# iso_lvds_tx.net
KiCad netlist of a schematic drawn in Altium Designer
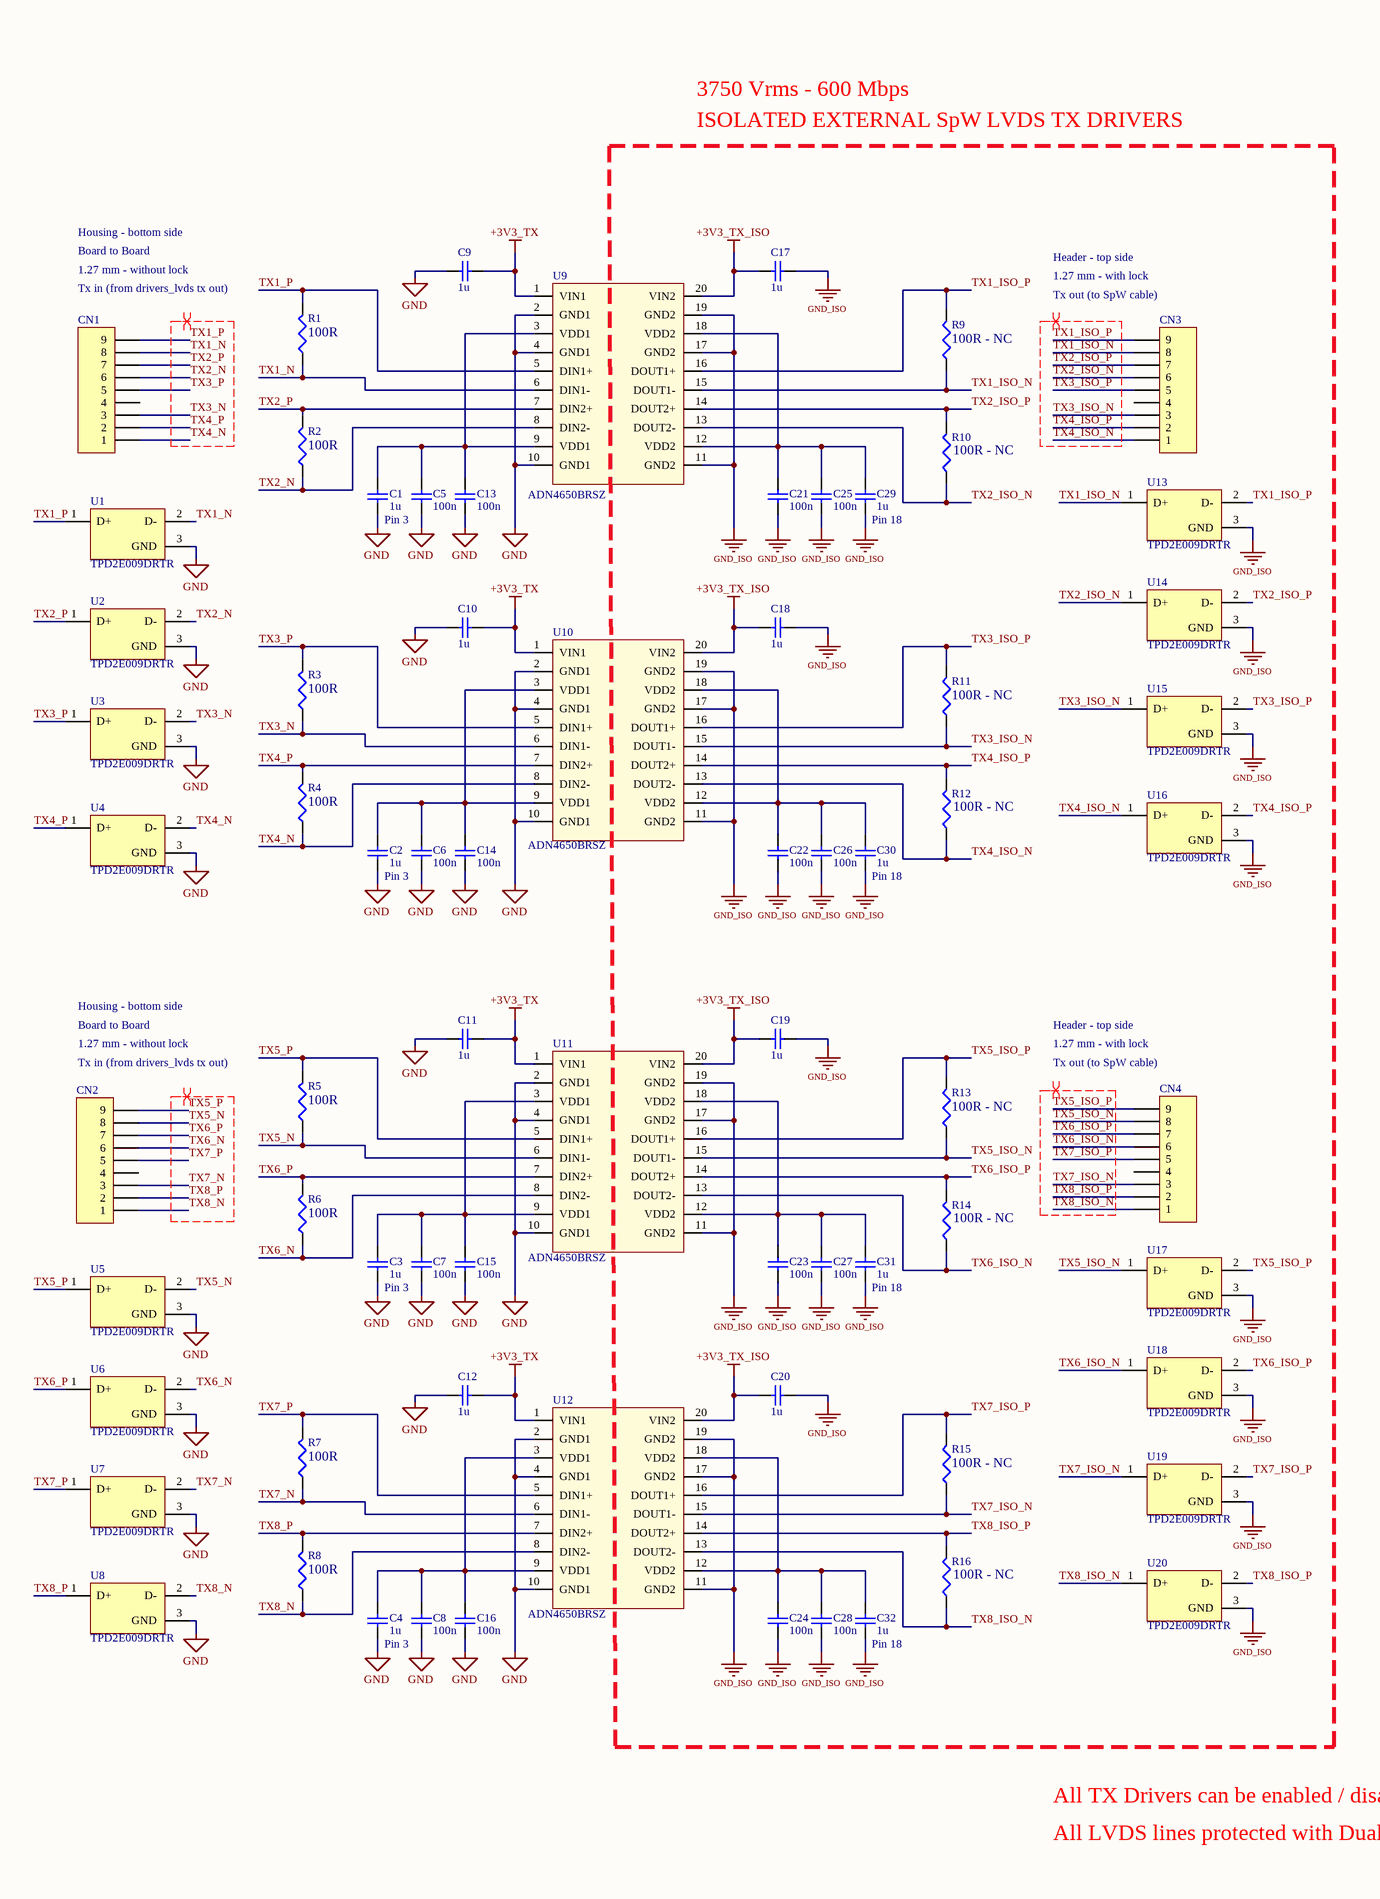
[diagram p0: iso_lvds_tx.SchDoc, left]
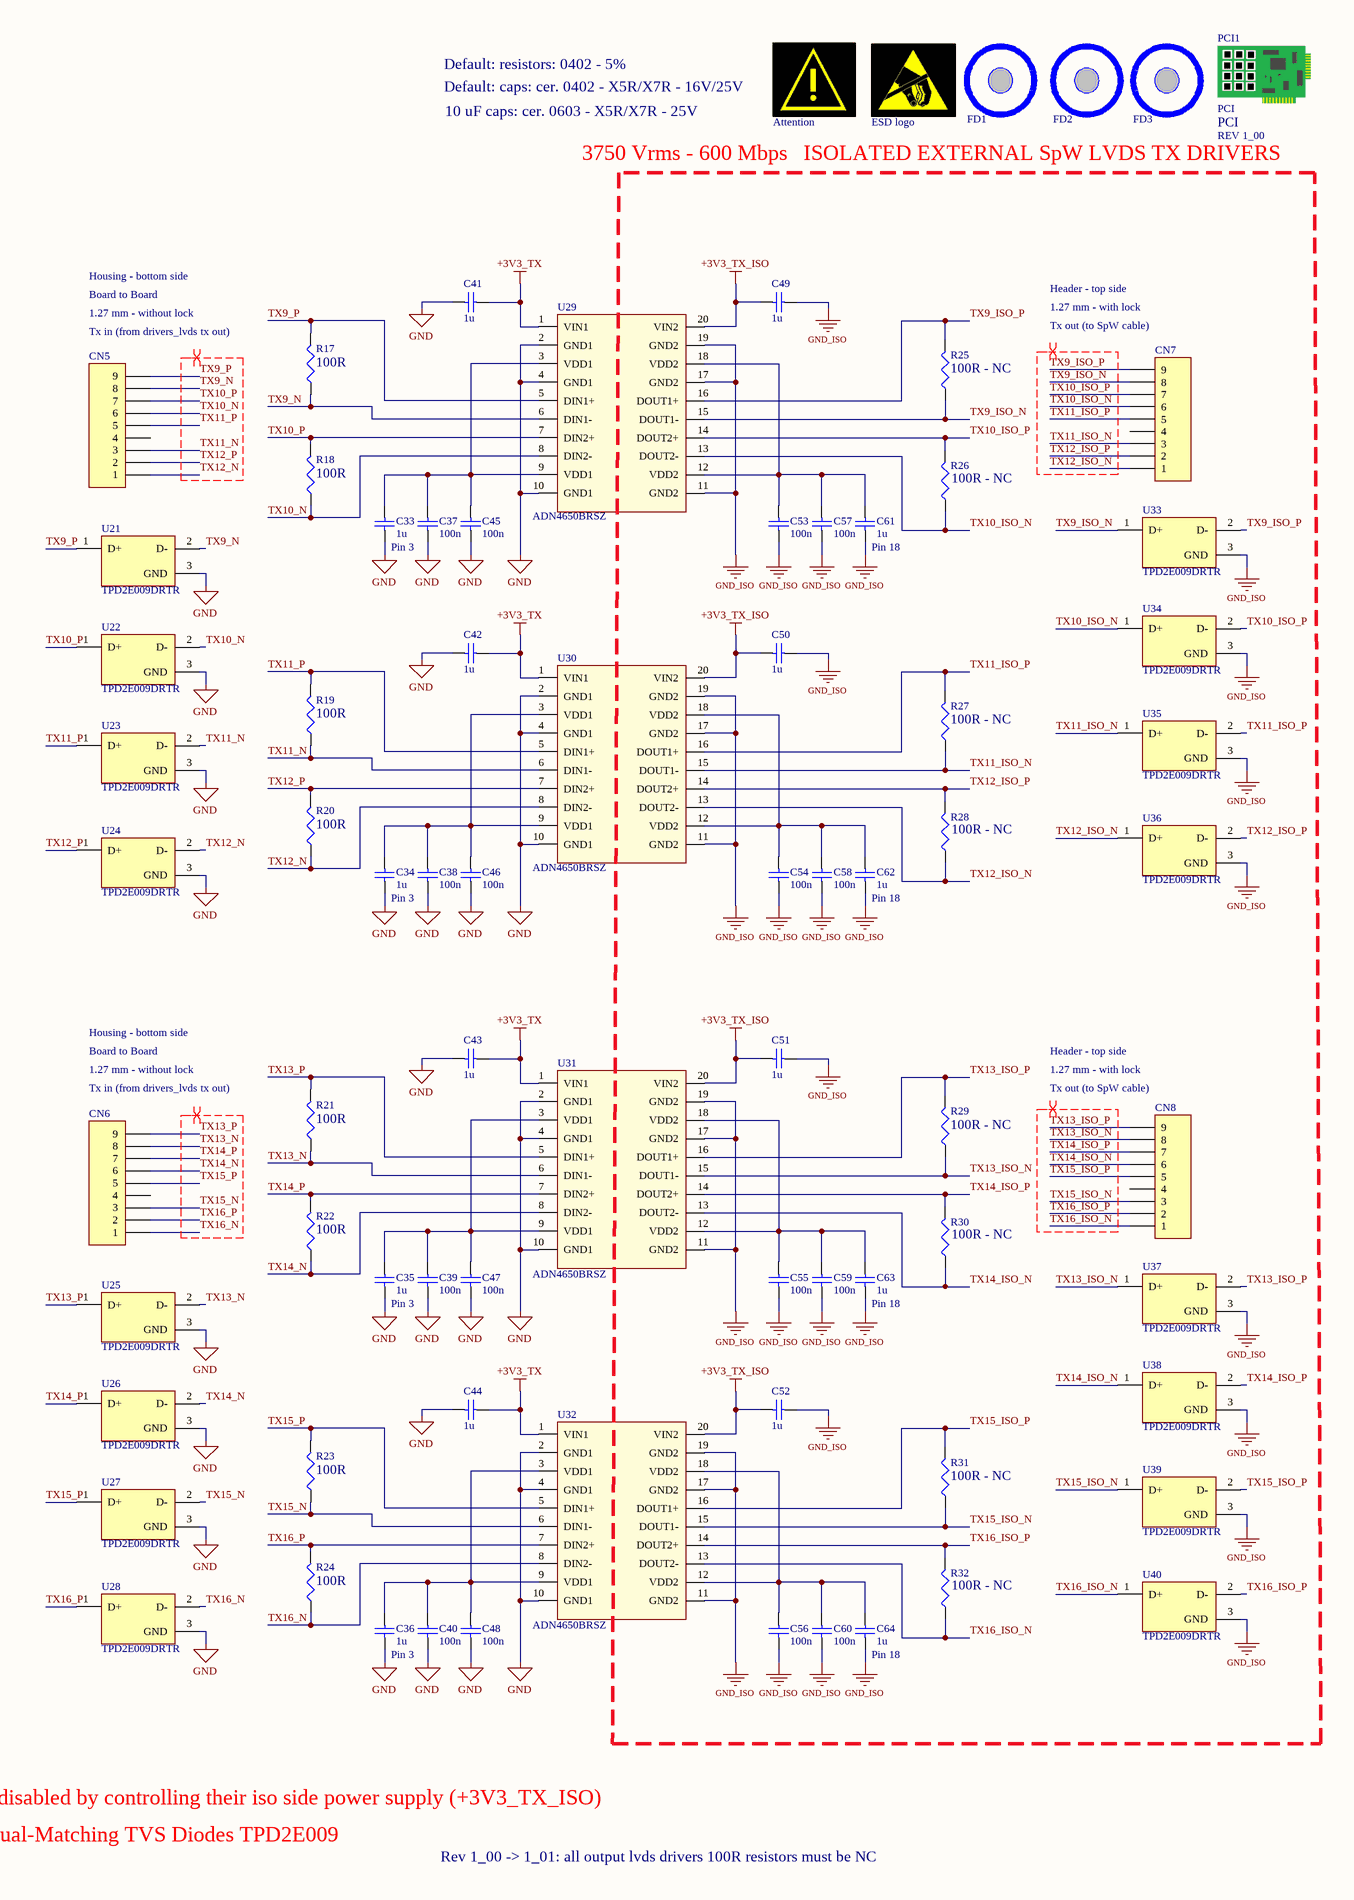
[diagram p1: iso_lvds_tx.SchDoc, right]

(export (version "E")
  (design (tool "Eeschema 10.0.6"))
  (components
    (comp (ref "AT1")
      (value "##nl")
      (footprint "LEIA_DOCUMENTACAO")
      (description "ATENCAO")
      (fields (field (name "VALOR") "Attention"))
      (libsource (lib "SIMBOLOS") (part "ATENCAO"))
    )
    (comp (ref "C1")
      (value "Capacitor Cerâmico SMD")
      (footprint "0402-cap")
      (fields (field (name "VALOR") "1u"))
      (libsource (lib "Miscellaneous Devices") (part "Capacitor Cerâmico SMD"))
    )
    (comp (ref "C2")
      (value "Capacitor Cerâmico SMD")
      (footprint "0402-cap")
      (fields (field (name "VALOR") "1u"))
      (libsource (lib "Miscellaneous Devices") (part "Capacitor Cerâmico SMD"))
    )
    (comp (ref "C3")
      (value "Capacitor Cerâmico SMD")
      (footprint "0402-cap")
      (fields (field (name "VALOR") "1u"))
      (libsource (lib "Miscellaneous Devices") (part "Capacitor Cerâmico SMD"))
    )
    (comp (ref "C4")
      (value "Capacitor Cerâmico SMD")
      (footprint "0402-cap")
      (fields (field (name "VALOR") "1u"))
      (libsource (lib "Miscellaneous Devices") (part "Capacitor Cerâmico SMD"))
    )
    (comp (ref "C5")
      (value "Capacitor Cerâmico SMD")
      (footprint "0402-cap")
      (fields (field (name "VALOR") "100n"))
      (libsource (lib "Miscellaneous Devices") (part "Capacitor Cerâmico SMD"))
    )
    (comp (ref "C6")
      (value "Capacitor Cerâmico SMD")
      (footprint "0402-cap")
      (fields (field (name "VALOR") "100n"))
      (libsource (lib "Miscellaneous Devices") (part "Capacitor Cerâmico SMD"))
    )
    (comp (ref "C7")
      (value "Capacitor Cerâmico SMD")
      (footprint "0402-cap")
      (fields (field (name "VALOR") "100n"))
      (libsource (lib "Miscellaneous Devices") (part "Capacitor Cerâmico SMD"))
    )
    (comp (ref "C8")
      (value "Capacitor Cerâmico SMD")
      (footprint "0402-cap")
      (fields (field (name "VALOR") "100n"))
      (libsource (lib "Miscellaneous Devices") (part "Capacitor Cerâmico SMD"))
    )
    (comp (ref "C9")
      (value "Capacitor Cerâmico SMD")
      (footprint "0402-cap")
      (fields (field (name "VALOR") "1u"))
      (libsource (lib "Miscellaneous Devices") (part "Capacitor Cerâmico SMD"))
    )
    (comp (ref "C10")
      (value "Capacitor Cerâmico SMD")
      (footprint "0402-cap")
      (fields (field (name "VALOR") "1u"))
      (libsource (lib "Miscellaneous Devices") (part "Capacitor Cerâmico SMD"))
    )
    (comp (ref "C11")
      (value "Capacitor Cerâmico SMD")
      (footprint "0402-cap")
      (fields (field (name "VALOR") "1u"))
      (libsource (lib "Miscellaneous Devices") (part "Capacitor Cerâmico SMD"))
    )
    (comp (ref "C12")
      (value "Capacitor Cerâmico SMD")
      (footprint "0402-cap")
      (fields (field (name "VALOR") "1u"))
      (libsource (lib "Miscellaneous Devices") (part "Capacitor Cerâmico SMD"))
    )
    (comp (ref "C13")
      (value "Capacitor Cerâmico SMD")
      (footprint "0402-cap")
      (fields (field (name "VALOR") "100n"))
      (libsource (lib "Miscellaneous Devices") (part "Capacitor Cerâmico SMD"))
    )
    (comp (ref "C14")
      (value "Capacitor Cerâmico SMD")
      (footprint "0402-cap")
      (fields (field (name "VALOR") "100n"))
      (libsource (lib "Miscellaneous Devices") (part "Capacitor Cerâmico SMD"))
    )
    (comp (ref "C15")
      (value "Capacitor Cerâmico SMD")
      (footprint "0402-cap")
      (fields (field (name "VALOR") "100n"))
      (libsource (lib "Miscellaneous Devices") (part "Capacitor Cerâmico SMD"))
    )
    (comp (ref "C16")
      (value "Capacitor Cerâmico SMD")
      (footprint "0402-cap")
      (fields (field (name "VALOR") "100n"))
      (libsource (lib "Miscellaneous Devices") (part "Capacitor Cerâmico SMD"))
    )
    (comp (ref "C17")
      (value "Capacitor Cerâmico SMD")
      (footprint "0402-cap")
      (fields (field (name "VALOR") "1u"))
      (libsource (lib "Miscellaneous Devices") (part "Capacitor Cerâmico SMD"))
    )
    (comp (ref "C18")
      (value "Capacitor Cerâmico SMD")
      (footprint "0402-cap")
      (fields (field (name "VALOR") "1u"))
      (libsource (lib "Miscellaneous Devices") (part "Capacitor Cerâmico SMD"))
    )
    (comp (ref "C19")
      (value "Capacitor Cerâmico SMD")
      (footprint "0402-cap")
      (fields (field (name "VALOR") "1u"))
      (libsource (lib "Miscellaneous Devices") (part "Capacitor Cerâmico SMD"))
    )
    (comp (ref "C20")
      (value "Capacitor Cerâmico SMD")
      (footprint "0402-cap")
      (fields (field (name "VALOR") "1u"))
      (libsource (lib "Miscellaneous Devices") (part "Capacitor Cerâmico SMD"))
    )
    (comp (ref "C21")
      (value "Capacitor Cerâmico SMD")
      (footprint "0402-cap")
      (fields (field (name "VALOR") "100n"))
      (libsource (lib "Miscellaneous Devices") (part "Capacitor Cerâmico SMD"))
    )
    (comp (ref "C22")
      (value "Capacitor Cerâmico SMD")
      (footprint "0402-cap")
      (fields (field (name "VALOR") "100n"))
      (libsource (lib "Miscellaneous Devices") (part "Capacitor Cerâmico SMD"))
    )
    (comp (ref "C23")
      (value "Capacitor Cerâmico SMD")
      (footprint "0402-cap")
      (fields (field (name "VALOR") "100n"))
      (libsource (lib "Miscellaneous Devices") (part "Capacitor Cerâmico SMD"))
    )
    (comp (ref "C24")
      (value "Capacitor Cerâmico SMD")
      (footprint "0402-cap")
      (fields (field (name "VALOR") "100n"))
      (libsource (lib "Miscellaneous Devices") (part "Capacitor Cerâmico SMD"))
    )
    (comp (ref "C25")
      (value "Capacitor Cerâmico SMD")
      (footprint "0402-cap")
      (fields (field (name "VALOR") "100n"))
      (libsource (lib "Miscellaneous Devices") (part "Capacitor Cerâmico SMD"))
    )
    (comp (ref "C26")
      (value "Capacitor Cerâmico SMD")
      (footprint "0402-cap")
      (fields (field (name "VALOR") "100n"))
      (libsource (lib "Miscellaneous Devices") (part "Capacitor Cerâmico SMD"))
    )
    (comp (ref "C27")
      (value "Capacitor Cerâmico SMD")
      (footprint "0402-cap")
      (fields (field (name "VALOR") "100n"))
      (libsource (lib "Miscellaneous Devices") (part "Capacitor Cerâmico SMD"))
    )
    (comp (ref "C28")
      (value "Capacitor Cerâmico SMD")
      (footprint "0402-cap")
      (fields (field (name "VALOR") "100n"))
      (libsource (lib "Miscellaneous Devices") (part "Capacitor Cerâmico SMD"))
    )
    (comp (ref "C29")
      (value "Capacitor Cerâmico SMD")
      (footprint "0402-cap")
      (fields (field (name "VALOR") "1u"))
      (libsource (lib "Miscellaneous Devices") (part "Capacitor Cerâmico SMD"))
    )
    (comp (ref "C30")
      (value "Capacitor Cerâmico SMD")
      (footprint "0402-cap")
      (fields (field (name "VALOR") "1u"))
      (libsource (lib "Miscellaneous Devices") (part "Capacitor Cerâmico SMD"))
    )
    (comp (ref "C31")
      (value "Capacitor Cerâmico SMD")
      (footprint "0402-cap")
      (fields (field (name "VALOR") "1u"))
      (libsource (lib "Miscellaneous Devices") (part "Capacitor Cerâmico SMD"))
    )
    (comp (ref "C32")
      (value "Capacitor Cerâmico SMD")
      (footprint "0402-cap")
      (fields (field (name "VALOR") "1u"))
      (libsource (lib "Miscellaneous Devices") (part "Capacitor Cerâmico SMD"))
    )
    (comp (ref "C33")
      (value "Capacitor Cerâmico SMD")
      (footprint "0402-cap")
      (fields (field (name "VALOR") "1u"))
      (libsource (lib "Miscellaneous Devices") (part "Capacitor Cerâmico SMD"))
    )
    (comp (ref "C34")
      (value "Capacitor Cerâmico SMD")
      (footprint "0402-cap")
      (fields (field (name "VALOR") "1u"))
      (libsource (lib "Miscellaneous Devices") (part "Capacitor Cerâmico SMD"))
    )
    (comp (ref "C35")
      (value "Capacitor Cerâmico SMD")
      (footprint "0402-cap")
      (fields (field (name "VALOR") "1u"))
      (libsource (lib "Miscellaneous Devices") (part "Capacitor Cerâmico SMD"))
    )
    (comp (ref "C36")
      (value "Capacitor Cerâmico SMD")
      (footprint "0402-cap")
      (fields (field (name "VALOR") "1u"))
      (libsource (lib "Miscellaneous Devices") (part "Capacitor Cerâmico SMD"))
    )
    (comp (ref "C37")
      (value "Capacitor Cerâmico SMD")
      (footprint "0402-cap")
      (fields (field (name "VALOR") "100n"))
      (libsource (lib "Miscellaneous Devices") (part "Capacitor Cerâmico SMD"))
    )
    (comp (ref "C38")
      (value "Capacitor Cerâmico SMD")
      (footprint "0402-cap")
      (fields (field (name "VALOR") "100n"))
      (libsource (lib "Miscellaneous Devices") (part "Capacitor Cerâmico SMD"))
    )
    (comp (ref "C39")
      (value "Capacitor Cerâmico SMD")
      (footprint "0402-cap")
      (fields (field (name "VALOR") "100n"))
      (libsource (lib "Miscellaneous Devices") (part "Capacitor Cerâmico SMD"))
    )
    (comp (ref "C40")
      (value "Capacitor Cerâmico SMD")
      (footprint "0402-cap")
      (fields (field (name "VALOR") "100n"))
      (libsource (lib "Miscellaneous Devices") (part "Capacitor Cerâmico SMD"))
    )
    (comp (ref "C41")
      (value "Capacitor Cerâmico SMD")
      (footprint "0402-cap")
      (fields (field (name "VALOR") "1u"))
      (libsource (lib "Miscellaneous Devices") (part "Capacitor Cerâmico SMD"))
    )
    (comp (ref "C42")
      (value "Capacitor Cerâmico SMD")
      (footprint "0402-cap")
      (fields (field (name "VALOR") "1u"))
      (libsource (lib "Miscellaneous Devices") (part "Capacitor Cerâmico SMD"))
    )
    (comp (ref "C43")
      (value "Capacitor Cerâmico SMD")
      (footprint "0402-cap")
      (fields (field (name "VALOR") "1u"))
      (libsource (lib "Miscellaneous Devices") (part "Capacitor Cerâmico SMD"))
    )
    (comp (ref "C44")
      (value "Capacitor Cerâmico SMD")
      (footprint "0402-cap")
      (fields (field (name "VALOR") "1u"))
      (libsource (lib "Miscellaneous Devices") (part "Capacitor Cerâmico SMD"))
    )
    (comp (ref "C45")
      (value "Capacitor Cerâmico SMD")
      (footprint "0402-cap")
      (fields (field (name "VALOR") "100n"))
      (libsource (lib "Miscellaneous Devices") (part "Capacitor Cerâmico SMD"))
    )
    (comp (ref "C46")
      (value "Capacitor Cerâmico SMD")
      (footprint "0402-cap")
      (fields (field (name "VALOR") "100n"))
      (libsource (lib "Miscellaneous Devices") (part "Capacitor Cerâmico SMD"))
    )
    (comp (ref "C47")
      (value "Capacitor Cerâmico SMD")
      (footprint "0402-cap")
      (fields (field (name "VALOR") "100n"))
      (libsource (lib "Miscellaneous Devices") (part "Capacitor Cerâmico SMD"))
    )
    (comp (ref "C48")
      (value "Capacitor Cerâmico SMD")
      (footprint "0402-cap")
      (fields (field (name "VALOR") "100n"))
      (libsource (lib "Miscellaneous Devices") (part "Capacitor Cerâmico SMD"))
    )
    (comp (ref "C49")
      (value "Capacitor Cerâmico SMD")
      (footprint "0402-cap")
      (fields (field (name "VALOR") "1u"))
      (libsource (lib "Miscellaneous Devices") (part "Capacitor Cerâmico SMD"))
    )
    (comp (ref "C50")
      (value "Capacitor Cerâmico SMD")
      (footprint "0402-cap")
      (fields (field (name "VALOR") "1u"))
      (libsource (lib "Miscellaneous Devices") (part "Capacitor Cerâmico SMD"))
    )
    (comp (ref "C51")
      (value "Capacitor Cerâmico SMD")
      (footprint "0402-cap")
      (fields (field (name "VALOR") "1u"))
      (libsource (lib "Miscellaneous Devices") (part "Capacitor Cerâmico SMD"))
    )
    (comp (ref "C52")
      (value "Capacitor Cerâmico SMD")
      (footprint "0402-cap")
      (fields (field (name "VALOR") "1u"))
      (libsource (lib "Miscellaneous Devices") (part "Capacitor Cerâmico SMD"))
    )
    (comp (ref "C53")
      (value "Capacitor Cerâmico SMD")
      (footprint "0402-cap")
      (fields (field (name "VALOR") "100n"))
      (libsource (lib "Miscellaneous Devices") (part "Capacitor Cerâmico SMD"))
    )
    (comp (ref "C54")
      (value "Capacitor Cerâmico SMD")
      (footprint "0402-cap")
      (fields (field (name "VALOR") "100n"))
      (libsource (lib "Miscellaneous Devices") (part "Capacitor Cerâmico SMD"))
    )
    (comp (ref "C55")
      (value "Capacitor Cerâmico SMD")
      (footprint "0402-cap")
      (fields (field (name "VALOR") "100n"))
      (libsource (lib "Miscellaneous Devices") (part "Capacitor Cerâmico SMD"))
    )
    (comp (ref "C56")
      (value "Capacitor Cerâmico SMD")
      (footprint "0402-cap")
      (fields (field (name "VALOR") "100n"))
      (libsource (lib "Miscellaneous Devices") (part "Capacitor Cerâmico SMD"))
    )
    (comp (ref "C57")
      (value "Capacitor Cerâmico SMD")
      (footprint "0402-cap")
      (fields (field (name "VALOR") "100n"))
      (libsource (lib "Miscellaneous Devices") (part "Capacitor Cerâmico SMD"))
    )
    (comp (ref "C58")
      (value "Capacitor Cerâmico SMD")
      (footprint "0402-cap")
      (fields (field (name "VALOR") "100n"))
      (libsource (lib "Miscellaneous Devices") (part "Capacitor Cerâmico SMD"))
    )
    (comp (ref "C59")
      (value "Capacitor Cerâmico SMD")
      (footprint "0402-cap")
      (fields (field (name "VALOR") "100n"))
      (libsource (lib "Miscellaneous Devices") (part "Capacitor Cerâmico SMD"))
    )
    (comp (ref "C60")
      (value "Capacitor Cerâmico SMD")
      (footprint "0402-cap")
      (fields (field (name "VALOR") "100n"))
      (libsource (lib "Miscellaneous Devices") (part "Capacitor Cerâmico SMD"))
    )
    (comp (ref "C61")
      (value "Capacitor Cerâmico SMD")
      (footprint "0402-cap")
      (fields (field (name "VALOR") "1u"))
      (libsource (lib "Miscellaneous Devices") (part "Capacitor Cerâmico SMD"))
    )
    (comp (ref "C62")
      (value "Capacitor Cerâmico SMD")
      (footprint "0402-cap")
      (fields (field (name "VALOR") "1u"))
      (libsource (lib "Miscellaneous Devices") (part "Capacitor Cerâmico SMD"))
    )
    (comp (ref "C63")
      (value "Capacitor Cerâmico SMD")
      (footprint "0402-cap")
      (fields (field (name "VALOR") "1u"))
      (libsource (lib "Miscellaneous Devices") (part "Capacitor Cerâmico SMD"))
    )
    (comp (ref "C64")
      (value "Capacitor Cerâmico SMD")
      (footprint "0402-cap")
      (fields (field (name "VALOR") "1u"))
      (libsource (lib "Miscellaneous Devices") (part "Capacitor Cerâmico SMD"))
    )
    (comp (ref "CN1")
      (value "MHDR1X9")
      (footprint "MHDR1X9_Axonn")
      (description "Header, 9-Pin")
      (fields (field (name "PUBLISHER") "Altium Limited"))
      (libsource (lib "") (part "MHDR1X9_1"))
    )
    (comp (ref "CN2")
      (value "MHDR1X9")
      (footprint "MHDR1X9_Axonn")
      (description "Header, 9-Pin")
      (fields (field (name "PUBLISHER") "Altium Limited"))
      (libsource (lib "") (part "MHDR1X9_1"))
    )
    (comp (ref "CN3")
      (value "MHDR1X9")
      (footprint "MHDR1X9_Axonn")
      (description "Header, 9-Pin")
      (fields (field (name "PUBLISHER") "Altium Limited"))
      (libsource (lib "Miscellaneous Connectors") (part "MHDR1X9"))
    )
    (comp (ref "CN4")
      (value "MHDR1X9")
      (footprint "MHDR1X9_Axonn")
      (description "Header, 9-Pin")
      (fields (field (name "PUBLISHER") "Altium Limited"))
      (libsource (lib "Miscellaneous Connectors") (part "MHDR1X9"))
    )
    (comp (ref "CN5")
      (value "MHDR1X9")
      (footprint "MHDR1X9_Axonn")
      (description "Header, 9-Pin")
      (fields (field (name "PUBLISHER") "Altium Limited"))
      (libsource (lib "") (part "MHDR1X9_1"))
    )
    (comp (ref "CN6")
      (value "MHDR1X9")
      (footprint "MHDR1X9_Axonn")
      (description "Header, 9-Pin")
      (fields (field (name "PUBLISHER") "Altium Limited"))
      (libsource (lib "") (part "MHDR1X9_1"))
    )
    (comp (ref "CN7")
      (value "MHDR1X9")
      (footprint "MHDR1X9_Axonn")
      (description "Header, 9-Pin")
      (fields (field (name "PUBLISHER") "Altium Limited"))
      (libsource (lib "Miscellaneous Connectors") (part "MHDR1X9"))
    )
    (comp (ref "CN8")
      (value "MHDR1X9")
      (footprint "MHDR1X9_Axonn")
      (description "Header, 9-Pin")
      (fields (field (name "PUBLISHER") "Altium Limited"))
      (libsource (lib "Miscellaneous Connectors") (part "MHDR1X9"))
    )
    (comp (ref "ESD1")
      (value "##nl")
      (footprint "ESTATICA")
      (description "ESD")
      (fields (field (name "VALOR") "ESD logo"))
      (libsource (lib "SIMBOLOS") (part "ESD"))
    )
    (comp (ref "FD1")
      (value "##nl")
      (footprint "FIDUCIAL")
      (description "Fiducial")
      (libsource (lib "PERIFERICOS") (part "Fiducial"))
    )
    (comp (ref "FD2")
      (value "##nl")
      (footprint "FIDUCIAL")
      (description "Fiducial")
      (libsource (lib "PERIFERICOS") (part "Fiducial"))
    )
    (comp (ref "FD3")
      (value "##nl")
      (footprint "FIDUCIAL")
      (description "Fiducial")
      (libsource (lib "PERIFERICOS") (part "Fiducial"))
    )
    (comp (ref "PCI1")
      (value "PCI")
      (fields (field (name "VALOR") "PCI") (field (name "REV") "REV 1_00"))
      (libsource (lib "PCI") (part "PCI"))
    )
    (comp (ref "R1")
      (value "Res3")
      (footprint "0402-res")
      (description "Resistor")
      (fields (field (name "VALOR") "100R"))
      (libsource (lib "Miscellaneous Devices") (part "Res3"))
    )
    (comp (ref "R2")
      (value "Res3")
      (footprint "0402-res")
      (description "Resistor")
      (fields (field (name "VALOR") "100R"))
      (libsource (lib "Miscellaneous Devices") (part "Res3"))
    )
    (comp (ref "R3")
      (value "Res3")
      (footprint "0402-res")
      (description "Resistor")
      (fields (field (name "VALOR") "100R"))
      (libsource (lib "Miscellaneous Devices") (part "Res3"))
    )
    (comp (ref "R4")
      (value "Res3")
      (footprint "0402-res")
      (description "Resistor")
      (fields (field (name "VALOR") "100R"))
      (libsource (lib "Miscellaneous Devices") (part "Res3"))
    )
    (comp (ref "R5")
      (value "Res3")
      (footprint "0402-res")
      (description "Resistor")
      (fields (field (name "VALOR") "100R"))
      (libsource (lib "Miscellaneous Devices") (part "Res3"))
    )
    (comp (ref "R6")
      (value "Res3")
      (footprint "0402-res")
      (description "Resistor")
      (fields (field (name "VALOR") "100R"))
      (libsource (lib "Miscellaneous Devices") (part "Res3"))
    )
    (comp (ref "R7")
      (value "Res3")
      (footprint "0402-res")
      (description "Resistor")
      (fields (field (name "VALOR") "100R"))
      (libsource (lib "Miscellaneous Devices") (part "Res3"))
    )
    (comp (ref "R8")
      (value "Res3")
      (footprint "0402-res")
      (description "Resistor")
      (fields (field (name "VALOR") "100R"))
      (libsource (lib "Miscellaneous Devices") (part "Res3"))
    )
    (comp (ref "R9")
      (value "Res3")
      (footprint "0402-res")
      (description "Resistor")
      (fields (field (name "VALOR") "100R - NC"))
      (libsource (lib "Miscellaneous Devices") (part "Res3"))
    )
    (comp (ref "R10")
      (value "Res3")
      (footprint "0402-res")
      (description "Resistor")
      (fields (field (name "VALOR") "100R - NC"))
      (libsource (lib "Miscellaneous Devices") (part "Res3"))
    )
    (comp (ref "R11")
      (value "Res3")
      (footprint "0402-res")
      (description "Resistor")
      (fields (field (name "VALOR") "100R - NC"))
      (libsource (lib "Miscellaneous Devices") (part "Res3"))
    )
    (comp (ref "R12")
      (value "Res3")
      (footprint "0402-res")
      (description "Resistor")
      (fields (field (name "VALOR") "100R - NC"))
      (libsource (lib "Miscellaneous Devices") (part "Res3"))
    )
    (comp (ref "R13")
      (value "Res3")
      (footprint "0402-res")
      (description "Resistor")
      (fields (field (name "VALOR") "100R - NC"))
      (libsource (lib "Miscellaneous Devices") (part "Res3"))
    )
    (comp (ref "R14")
      (value "Res3")
      (footprint "0402-res")
      (description "Resistor")
      (fields (field (name "VALOR") "100R - NC"))
      (libsource (lib "Miscellaneous Devices") (part "Res3"))
    )
    (comp (ref "R15")
      (value "Res3")
      (footprint "0402-res")
      (description "Resistor")
      (fields (field (name "VALOR") "100R - NC"))
      (libsource (lib "Miscellaneous Devices") (part "Res3"))
    )
    (comp (ref "R16")
      (value "Res3")
      (footprint "0402-res")
      (description "Resistor")
      (fields (field (name "VALOR") "100R - NC"))
      (libsource (lib "Miscellaneous Devices") (part "Res3"))
    )
    (comp (ref "R17")
      (value "Res3")
      (footprint "0402-res")
      (description "Resistor")
      (fields (field (name "VALOR") "100R"))
      (libsource (lib "Miscellaneous Devices") (part "Res3"))
    )
    (comp (ref "R18")
      (value "Res3")
      (footprint "0402-res")
      (description "Resistor")
      (fields (field (name "VALOR") "100R"))
      (libsource (lib "Miscellaneous Devices") (part "Res3"))
    )
    (comp (ref "R19")
      (value "Res3")
      (footprint "0402-res")
      (description "Resistor")
      (fields (field (name "VALOR") "100R"))
      (libsource (lib "Miscellaneous Devices") (part "Res3"))
    )
    (comp (ref "R20")
      (value "Res3")
      (footprint "0402-res")
      (description "Resistor")
      (fields (field (name "VALOR") "100R"))
      (libsource (lib "Miscellaneous Devices") (part "Res3"))
    )
    (comp (ref "R21")
      (value "Res3")
      (footprint "0402-res")
      (description "Resistor")
      (fields (field (name "VALOR") "100R"))
      (libsource (lib "Miscellaneous Devices") (part "Res3"))
    )
    (comp (ref "R22")
      (value "Res3")
      (footprint "0402-res")
      (description "Resistor")
      (fields (field (name "VALOR") "100R"))
      (libsource (lib "Miscellaneous Devices") (part "Res3"))
    )
    (comp (ref "R23")
      (value "Res3")
      (footprint "0402-res")
      (description "Resistor")
      (fields (field (name "VALOR") "100R"))
      (libsource (lib "Miscellaneous Devices") (part "Res3"))
    )
    (comp (ref "R24")
      (value "Res3")
      (footprint "0402-res")
      (description "Resistor")
      (fields (field (name "VALOR") "100R"))
      (libsource (lib "Miscellaneous Devices") (part "Res3"))
    )
    (comp (ref "R25")
      (value "Res3")
      (footprint "0402-res")
      (description "Resistor")
      (fields (field (name "VALOR") "100R - NC"))
      (libsource (lib "Miscellaneous Devices") (part "Res3"))
    )
    (comp (ref "R26")
      (value "Res3")
      (footprint "0402-res")
      (description "Resistor")
      (fields (field (name "VALOR") "100R - NC"))
      (libsource (lib "Miscellaneous Devices") (part "Res3"))
    )
    (comp (ref "R27")
      (value "Res3")
      (footprint "0402-res")
      (description "Resistor")
      (fields (field (name "VALOR") "100R - NC"))
      (libsource (lib "Miscellaneous Devices") (part "Res3"))
    )
    (comp (ref "R28")
      (value "Res3")
      (footprint "0402-res")
      (description "Resistor")
      (fields (field (name "VALOR") "100R - NC"))
      (libsource (lib "Miscellaneous Devices") (part "Res3"))
    )
    (comp (ref "R29")
      (value "Res3")
      (footprint "0402-res")
      (description "Resistor")
      (fields (field (name "VALOR") "100R - NC"))
      (libsource (lib "Miscellaneous Devices") (part "Res3"))
    )
    (comp (ref "R30")
      (value "Res3")
      (footprint "0402-res")
      (description "Resistor")
      (fields (field (name "VALOR") "100R - NC"))
      (libsource (lib "Miscellaneous Devices") (part "Res3"))
    )
    (comp (ref "R31")
      (value "Res3")
      (footprint "0402-res")
      (description "Resistor")
      (fields (field (name "VALOR") "100R - NC"))
      (libsource (lib "Miscellaneous Devices") (part "Res3"))
    )
    (comp (ref "R32")
      (value "Res3")
      (footprint "0402-res")
      (description "Resistor")
      (fields (field (name "VALOR") "100R - NC"))
      (libsource (lib "Miscellaneous Devices") (part "Res3"))
    )
    (comp (ref "U1")
      (value "TPD2E009DRTR")
      (footprint "DRT3")
      (fields (field (name "MANUFACTURER") "Texas Instruments"))
      (libsource (lib "TI Interface ESD EMI Protection") (part "TPD2E009DRTR"))
    )
    (comp (ref "U2")
      (value "TPD2E009DRTR")
      (footprint "DRT3")
      (fields (field (name "MANUFACTURER") "Texas Instruments"))
      (libsource (lib "TI Interface ESD EMI Protection") (part "TPD2E009DRTR"))
    )
    (comp (ref "U3")
      (value "TPD2E009DRTR")
      (footprint "DRT3")
      (fields (field (name "MANUFACTURER") "Texas Instruments"))
      (libsource (lib "TI Interface ESD EMI Protection") (part "TPD2E009DRTR"))
    )
    (comp (ref "U4")
      (value "TPD2E009DRTR")
      (footprint "DRT3")
      (fields (field (name "MANUFACTURER") "Texas Instruments"))
      (libsource (lib "TI Interface ESD EMI Protection") (part "TPD2E009DRTR"))
    )
    (comp (ref "U5")
      (value "TPD2E009DRTR")
      (footprint "DRT3")
      (fields (field (name "MANUFACTURER") "Texas Instruments"))
      (libsource (lib "TI Interface ESD EMI Protection") (part "TPD2E009DRTR"))
    )
    (comp (ref "U6")
      (value "TPD2E009DRTR")
      (footprint "DRT3")
      (fields (field (name "MANUFACTURER") "Texas Instruments"))
      (libsource (lib "TI Interface ESD EMI Protection") (part "TPD2E009DRTR"))
    )
    (comp (ref "U7")
      (value "TPD2E009DRTR")
      (footprint "DRT3")
      (fields (field (name "MANUFACTURER") "Texas Instruments"))
      (libsource (lib "TI Interface ESD EMI Protection") (part "TPD2E009DRTR"))
    )
    (comp (ref "U8")
      (value "TPD2E009DRTR")
      (footprint "DRT3")
      (fields (field (name "MANUFACTURER") "Texas Instruments"))
      (libsource (lib "TI Interface ESD EMI Protection") (part "TPD2E009DRTR"))
    )
    (comp (ref "U9")
      (value "ADN4650BRSZ")
      (footprint "SSOP-RS-20")
      (description "5 kV RMS/3.75 kV RMS, 600 Mbps,  Dual-Channel LVDS Isolators")
      (fields (field (name "PART NUMBER") "ADN4650BRSZ"))
      (libsource (lib "lvds_isolators") (part "ADN4650BRSZ"))
    )
    (comp (ref "U10")
      (value "ADN4650BRSZ")
      (footprint "SSOP-RS-20")
      (description "5 kV RMS/3.75 kV RMS, 600 Mbps,  Dual-Channel LVDS Isolators")
      (fields (field (name "PART NUMBER") "ADN4650BRSZ"))
      (libsource (lib "lvds_isolators") (part "ADN4650BRSZ"))
    )
    (comp (ref "U11")
      (value "ADN4650BRSZ")
      (footprint "SSOP-RS-20")
      (description "5 kV RMS/3.75 kV RMS, 600 Mbps,  Dual-Channel LVDS Isolators")
      (fields (field (name "PART NUMBER") "ADN4650BRSZ"))
      (libsource (lib "lvds_isolators") (part "ADN4650BRSZ"))
    )
    (comp (ref "U12")
      (value "ADN4650BRSZ")
      (footprint "SSOP-RS-20")
      (description "5 kV RMS/3.75 kV RMS, 600 Mbps,  Dual-Channel LVDS Isolators")
      (fields (field (name "PART NUMBER") "ADN4650BRSZ"))
      (libsource (lib "lvds_isolators") (part "ADN4650BRSZ"))
    )
    (comp (ref "U13")
      (value "TPD2E009DRTR")
      (footprint "DRT3")
      (fields (field (name "MANUFACTURER") "Texas Instruments"))
      (libsource (lib "TI Interface ESD EMI Protection") (part "TPD2E009DRTR"))
    )
    (comp (ref "U14")
      (value "TPD2E009DRTR")
      (footprint "DRT3")
      (fields (field (name "MANUFACTURER") "Texas Instruments"))
      (libsource (lib "TI Interface ESD EMI Protection") (part "TPD2E009DRTR"))
    )
    (comp (ref "U15")
      (value "TPD2E009DRTR")
      (footprint "DRT3")
      (fields (field (name "MANUFACTURER") "Texas Instruments"))
      (libsource (lib "TI Interface ESD EMI Protection") (part "TPD2E009DRTR"))
    )
    (comp (ref "U16")
      (value "TPD2E009DRTR")
      (footprint "DRT3")
      (fields (field (name "MANUFACTURER") "Texas Instruments"))
      (libsource (lib "TI Interface ESD EMI Protection") (part "TPD2E009DRTR"))
    )
    (comp (ref "U17")
      (value "TPD2E009DRTR")
      (footprint "DRT3")
      (fields (field (name "MANUFACTURER") "Texas Instruments"))
      (libsource (lib "TI Interface ESD EMI Protection") (part "TPD2E009DRTR"))
    )
    (comp (ref "U18")
      (value "TPD2E009DRTR")
      (footprint "DRT3")
      (fields (field (name "MANUFACTURER") "Texas Instruments"))
      (libsource (lib "TI Interface ESD EMI Protection") (part "TPD2E009DRTR"))
    )
    (comp (ref "U19")
      (value "TPD2E009DRTR")
      (footprint "DRT3")
      (fields (field (name "MANUFACTURER") "Texas Instruments"))
      (libsource (lib "TI Interface ESD EMI Protection") (part "TPD2E009DRTR"))
    )
    (comp (ref "U20")
      (value "TPD2E009DRTR")
      (footprint "DRT3")
      (fields (field (name "MANUFACTURER") "Texas Instruments"))
      (libsource (lib "TI Interface ESD EMI Protection") (part "TPD2E009DRTR"))
    )
    (comp (ref "U21")
      (value "TPD2E009DRTR")
      (footprint "DRT3")
      (fields (field (name "MANUFACTURER") "Texas Instruments"))
      (libsource (lib "TI Interface ESD EMI Protection") (part "TPD2E009DRTR"))
    )
    (comp (ref "U22")
      (value "TPD2E009DRTR")
      (footprint "DRT3")
      (fields (field (name "MANUFACTURER") "Texas Instruments"))
      (libsource (lib "TI Interface ESD EMI Protection") (part "TPD2E009DRTR"))
    )
    (comp (ref "U23")
      (value "TPD2E009DRTR")
      (footprint "DRT3")
      (fields (field (name "MANUFACTURER") "Texas Instruments"))
      (libsource (lib "TI Interface ESD EMI Protection") (part "TPD2E009DRTR"))
    )
    (comp (ref "U24")
      (value "TPD2E009DRTR")
      (footprint "DRT3")
      (fields (field (name "MANUFACTURER") "Texas Instruments"))
      (libsource (lib "TI Interface ESD EMI Protection") (part "TPD2E009DRTR"))
    )
    (comp (ref "U25")
      (value "TPD2E009DRTR")
      (footprint "DRT3")
      (fields (field (name "MANUFACTURER") "Texas Instruments"))
      (libsource (lib "TI Interface ESD EMI Protection") (part "TPD2E009DRTR"))
    )
    (comp (ref "U26")
      (value "TPD2E009DRTR")
      (footprint "DRT3")
      (fields (field (name "MANUFACTURER") "Texas Instruments"))
      (libsource (lib "TI Interface ESD EMI Protection") (part "TPD2E009DRTR"))
    )
    (comp (ref "U27")
      (value "TPD2E009DRTR")
      (footprint "DRT3")
      (fields (field (name "MANUFACTURER") "Texas Instruments"))
      (libsource (lib "TI Interface ESD EMI Protection") (part "TPD2E009DRTR"))
    )
    (comp (ref "U28")
      (value "TPD2E009DRTR")
      (footprint "DRT3")
      (fields (field (name "MANUFACTURER") "Texas Instruments"))
      (libsource (lib "TI Interface ESD EMI Protection") (part "TPD2E009DRTR"))
    )
    (comp (ref "U29")
      (value "ADN4650BRSZ")
      (footprint "SSOP-RS-20")
      (description "5 kV RMS/3.75 kV RMS, 600 Mbps,  Dual-Channel LVDS Isolators")
      (fields (field (name "PART NUMBER") "ADN4650BRSZ"))
      (libsource (lib "lvds_isolators") (part "ADN4650BRSZ"))
    )
    (comp (ref "U30")
      (value "ADN4650BRSZ")
      (footprint "SSOP-RS-20")
      (description "5 kV RMS/3.75 kV RMS, 600 Mbps,  Dual-Channel LVDS Isolators")
      (fields (field (name "PART NUMBER") "ADN4650BRSZ"))
      (libsource (lib "lvds_isolators") (part "ADN4650BRSZ"))
    )
    (comp (ref "U31")
      (value "ADN4650BRSZ")
      (footprint "SSOP-RS-20")
      (description "5 kV RMS/3.75 kV RMS, 600 Mbps,  Dual-Channel LVDS Isolators")
      (fields (field (name "PART NUMBER") "ADN4650BRSZ"))
      (libsource (lib "lvds_isolators") (part "ADN4650BRSZ"))
    )
    (comp (ref "U32")
      (value "ADN4650BRSZ")
      (footprint "SSOP-RS-20")
      (description "5 kV RMS/3.75 kV RMS, 600 Mbps,  Dual-Channel LVDS Isolators")
      (fields (field (name "PART NUMBER") "ADN4650BRSZ"))
      (libsource (lib "lvds_isolators") (part "ADN4650BRSZ"))
    )
    (comp (ref "U33")
      (value "TPD2E009DRTR")
      (footprint "DRT3")
      (fields (field (name "MANUFACTURER") "Texas Instruments"))
      (libsource (lib "TI Interface ESD EMI Protection") (part "TPD2E009DRTR"))
    )
    (comp (ref "U34")
      (value "TPD2E009DRTR")
      (footprint "DRT3")
      (fields (field (name "MANUFACTURER") "Texas Instruments"))
      (libsource (lib "TI Interface ESD EMI Protection") (part "TPD2E009DRTR"))
    )
    (comp (ref "U35")
      (value "TPD2E009DRTR")
      (footprint "DRT3")
      (fields (field (name "MANUFACTURER") "Texas Instruments"))
      (libsource (lib "TI Interface ESD EMI Protection") (part "TPD2E009DRTR"))
    )
    (comp (ref "U36")
      (value "TPD2E009DRTR")
      (footprint "DRT3")
      (fields (field (name "MANUFACTURER") "Texas Instruments"))
      (libsource (lib "TI Interface ESD EMI Protection") (part "TPD2E009DRTR"))
    )
    (comp (ref "U37")
      (value "TPD2E009DRTR")
      (footprint "DRT3")
      (fields (field (name "MANUFACTURER") "Texas Instruments"))
      (libsource (lib "TI Interface ESD EMI Protection") (part "TPD2E009DRTR"))
    )
    (comp (ref "U38")
      (value "TPD2E009DRTR")
      (footprint "DRT3")
      (fields (field (name "MANUFACTURER") "Texas Instruments"))
      (libsource (lib "TI Interface ESD EMI Protection") (part "TPD2E009DRTR"))
    )
    (comp (ref "U39")
      (value "TPD2E009DRTR")
      (footprint "DRT3")
      (fields (field (name "MANUFACTURER") "Texas Instruments"))
      (libsource (lib "TI Interface ESD EMI Protection") (part "TPD2E009DRTR"))
    )
    (comp (ref "U40")
      (value "TPD2E009DRTR")
      (footprint "DRT3")
      (fields (field (name "MANUFACTURER") "Texas Instruments"))
      (libsource (lib "TI Interface ESD EMI Protection") (part "TPD2E009DRTR"))
    )
  )
  (nets
    (net (code "1") (name "+3V3_TX") (class "Default")
      (node (ref "C10") (pin "1") (pinfunction "1_1") (pintype "passive"))
      (node (ref "C11") (pin "1") (pinfunction "1_1") (pintype "passive"))
      (node (ref "C12") (pin "1") (pinfunction "1_1") (pintype "passive"))
      (node (ref "C41") (pin "1") (pinfunction "1_1") (pintype "passive"))
      (node (ref "C42") (pin "1") (pinfunction "1_1") (pintype "passive"))
      (node (ref "C43") (pin "1") (pinfunction "1_1") (pintype "passive"))
      (node (ref "C44") (pin "1") (pinfunction "1_1") (pintype "passive"))
      (node (ref "C9") (pin "1") (pinfunction "1_1") (pintype "passive"))
      (node (ref "U10") (pin "1") (pinfunction "VIN1_1") (pintype "passive"))
      (node (ref "U11") (pin "1") (pinfunction "VIN1_1") (pintype "passive"))
      (node (ref "U12") (pin "1") (pinfunction "VIN1_1") (pintype "passive"))
      (node (ref "U29") (pin "1") (pinfunction "VIN1_1") (pintype "passive"))
      (node (ref "U30") (pin "1") (pinfunction "VIN1_1") (pintype "passive"))
      (node (ref "U31") (pin "1") (pinfunction "VIN1_1") (pintype "passive"))
      (node (ref "U32") (pin "1") (pinfunction "VIN1_1") (pintype "passive"))
      (node (ref "U9") (pin "1") (pinfunction "VIN1_1") (pintype "passive"))
    )
    (net (code "2") (name "+3V3_TX_ISO") (class "Default")
      (node (ref "C17") (pin "2") (pinfunction "2_2") (pintype "passive"))
      (node (ref "C18") (pin "2") (pinfunction "2_2") (pintype "passive"))
      (node (ref "C19") (pin "2") (pinfunction "2_2") (pintype "passive"))
      (node (ref "C20") (pin "2") (pinfunction "2_2") (pintype "passive"))
      (node (ref "C49") (pin "2") (pinfunction "2_2") (pintype "passive"))
      (node (ref "C50") (pin "2") (pinfunction "2_2") (pintype "passive"))
      (node (ref "C51") (pin "2") (pinfunction "2_2") (pintype "passive"))
      (node (ref "C52") (pin "2") (pinfunction "2_2") (pintype "passive"))
      (node (ref "U10") (pin "20") (pinfunction "VIN2_20") (pintype "passive"))
      (node (ref "U11") (pin "20") (pinfunction "VIN2_20") (pintype "passive"))
      (node (ref "U12") (pin "20") (pinfunction "VIN2_20") (pintype "passive"))
      (node (ref "U29") (pin "20") (pinfunction "VIN2_20") (pintype "passive"))
      (node (ref "U30") (pin "20") (pinfunction "VIN2_20") (pintype "passive"))
      (node (ref "U31") (pin "20") (pinfunction "VIN2_20") (pintype "passive"))
      (node (ref "U32") (pin "20") (pinfunction "VIN2_20") (pintype "passive"))
      (node (ref "U9") (pin "20") (pinfunction "VIN2_20") (pintype "passive"))
    )
    (net (code "3") (name "/TX1_ISO_N") (class "Default")
      (node (ref "CN3") (pin "8") (pinfunction "8_8") (pintype "passive"))
      (node (ref "R9") (pin "1") (pinfunction "1_1") (pintype "passive"))
      (node (ref "U13") (pin "1") (pinfunction "D+_1") (pintype "passive"))
      (node (ref "U9") (pin "15") (pinfunction "DOUT1-_15") (pintype "passive"))
    )
    (net (code "4") (name "/TX1_ISO_P") (class "Default")
      (node (ref "CN3") (pin "9") (pinfunction "9_9") (pintype "passive"))
      (node (ref "R9") (pin "2") (pinfunction "2_2") (pintype "passive"))
      (node (ref "U13") (pin "2") (pinfunction "D-_2") (pintype "passive"))
      (node (ref "U9") (pin "16") (pinfunction "DOUT1+_16") (pintype "passive"))
    )
    (net (code "5") (name "/TX1_N") (class "Default")
      (node (ref "CN1") (pin "8") (pinfunction "8_8") (pintype "passive"))
      (node (ref "R1") (pin "1") (pinfunction "1_1") (pintype "passive"))
      (node (ref "U1") (pin "2") (pinfunction "D-_2") (pintype "passive"))
      (node (ref "U9") (pin "6") (pinfunction "DIN1-_6") (pintype "passive"))
    )
    (net (code "6") (name "/TX1_P") (class "Default")
      (node (ref "CN1") (pin "9") (pinfunction "9_9") (pintype "passive"))
      (node (ref "R1") (pin "2") (pinfunction "2_2") (pintype "passive"))
      (node (ref "U1") (pin "1") (pinfunction "D+_1") (pintype "passive"))
      (node (ref "U9") (pin "5") (pinfunction "DIN1+_5") (pintype "passive"))
    )
    (net (code "7") (name "/TX2_ISO_N") (class "Default")
      (node (ref "CN3") (pin "6") (pinfunction "6_6") (pintype "passive"))
      (node (ref "R10") (pin "1") (pinfunction "1_1") (pintype "passive"))
      (node (ref "U14") (pin "1") (pinfunction "D+_1") (pintype "passive"))
      (node (ref "U9") (pin "13") (pinfunction "DOUT2-_13") (pintype "passive"))
    )
    (net (code "8") (name "/TX2_ISO_P") (class "Default")
      (node (ref "CN3") (pin "7") (pinfunction "7_7") (pintype "passive"))
      (node (ref "R10") (pin "2") (pinfunction "2_2") (pintype "passive"))
      (node (ref "U14") (pin "2") (pinfunction "D-_2") (pintype "passive"))
      (node (ref "U9") (pin "14") (pinfunction "DOUT2+_14") (pintype "passive"))
    )
    (net (code "9") (name "/TX2_N") (class "Default")
      (node (ref "CN1") (pin "6") (pinfunction "6_6") (pintype "passive"))
      (node (ref "R2") (pin "1") (pinfunction "1_1") (pintype "passive"))
      (node (ref "U2") (pin "2") (pinfunction "D-_2") (pintype "passive"))
      (node (ref "U9") (pin "8") (pinfunction "DIN2-_8") (pintype "passive"))
    )
    (net (code "10") (name "/TX2_P") (class "Default")
      (node (ref "CN1") (pin "7") (pinfunction "7_7") (pintype "passive"))
      (node (ref "R2") (pin "2") (pinfunction "2_2") (pintype "passive"))
      (node (ref "U2") (pin "1") (pinfunction "D+_1") (pintype "passive"))
      (node (ref "U9") (pin "7") (pinfunction "DIN2+_7") (pintype "passive"))
    )
    (net (code "11") (name "/TX3_ISO_N") (class "Default")
      (node (ref "CN3") (pin "3") (pinfunction "3_3") (pintype "passive"))
      (node (ref "R11") (pin "1") (pinfunction "1_1") (pintype "passive"))
      (node (ref "U10") (pin "15") (pinfunction "DOUT1-_15") (pintype "passive"))
      (node (ref "U15") (pin "1") (pinfunction "D+_1") (pintype "passive"))
    )
    (net (code "12") (name "/TX3_ISO_P") (class "Default")
      (node (ref "CN3") (pin "5") (pinfunction "5_5") (pintype "passive"))
      (node (ref "R11") (pin "2") (pinfunction "2_2") (pintype "passive"))
      (node (ref "U10") (pin "16") (pinfunction "DOUT1+_16") (pintype "passive"))
      (node (ref "U15") (pin "2") (pinfunction "D-_2") (pintype "passive"))
    )
    (net (code "13") (name "/TX3_N") (class "Default")
      (node (ref "CN1") (pin "3") (pinfunction "3_3") (pintype "passive"))
      (node (ref "R3") (pin "1") (pinfunction "1_1") (pintype "passive"))
      (node (ref "U10") (pin "6") (pinfunction "DIN1-_6") (pintype "passive"))
      (node (ref "U3") (pin "2") (pinfunction "D-_2") (pintype "passive"))
    )
    (net (code "14") (name "/TX3_P") (class "Default")
      (node (ref "CN1") (pin "5") (pinfunction "5_5") (pintype "passive"))
      (node (ref "R3") (pin "2") (pinfunction "2_2") (pintype "passive"))
      (node (ref "U10") (pin "5") (pinfunction "DIN1+_5") (pintype "passive"))
      (node (ref "U3") (pin "1") (pinfunction "D+_1") (pintype "passive"))
    )
    (net (code "15") (name "/TX4_ISO_N") (class "Default")
      (node (ref "CN3") (pin "1") (pinfunction "1_1") (pintype "passive"))
      (node (ref "R12") (pin "1") (pinfunction "1_1") (pintype "passive"))
      (node (ref "U10") (pin "13") (pinfunction "DOUT2-_13") (pintype "passive"))
      (node (ref "U16") (pin "1") (pinfunction "D+_1") (pintype "passive"))
    )
    (net (code "16") (name "/TX4_ISO_P") (class "Default")
      (node (ref "CN3") (pin "2") (pinfunction "2_2") (pintype "passive"))
      (node (ref "R12") (pin "2") (pinfunction "2_2") (pintype "passive"))
      (node (ref "U10") (pin "14") (pinfunction "DOUT2+_14") (pintype "passive"))
      (node (ref "U16") (pin "2") (pinfunction "D-_2") (pintype "passive"))
    )
    (net (code "17") (name "/TX4_N") (class "Default")
      (node (ref "CN1") (pin "1") (pinfunction "1_1") (pintype "passive"))
      (node (ref "R4") (pin "1") (pinfunction "1_1") (pintype "passive"))
      (node (ref "U10") (pin "8") (pinfunction "DIN2-_8") (pintype "passive"))
      (node (ref "U4") (pin "2") (pinfunction "D-_2") (pintype "passive"))
    )
    (net (code "18") (name "/TX4_P") (class "Default")
      (node (ref "CN1") (pin "2") (pinfunction "2_2") (pintype "passive"))
      (node (ref "R4") (pin "2") (pinfunction "2_2") (pintype "passive"))
      (node (ref "U10") (pin "7") (pinfunction "DIN2+_7") (pintype "passive"))
      (node (ref "U4") (pin "1") (pinfunction "D+_1") (pintype "passive"))
    )
    (net (code "19") (name "/TX5_ISO_N") (class "Default")
      (node (ref "CN4") (pin "8") (pinfunction "8_8") (pintype "passive"))
      (node (ref "R13") (pin "1") (pinfunction "1_1") (pintype "passive"))
      (node (ref "U11") (pin "15") (pinfunction "DOUT1-_15") (pintype "passive"))
      (node (ref "U17") (pin "1") (pinfunction "D+_1") (pintype "passive"))
    )
    (net (code "20") (name "/TX5_ISO_P") (class "Default")
      (node (ref "CN4") (pin "9") (pinfunction "9_9") (pintype "passive"))
      (node (ref "R13") (pin "2") (pinfunction "2_2") (pintype "passive"))
      (node (ref "U11") (pin "16") (pinfunction "DOUT1+_16") (pintype "passive"))
      (node (ref "U17") (pin "2") (pinfunction "D-_2") (pintype "passive"))
    )
    (net (code "21") (name "/TX5_N") (class "Default")
      (node (ref "CN2") (pin "8") (pinfunction "8_8") (pintype "passive"))
      (node (ref "R5") (pin "1") (pinfunction "1_1") (pintype "passive"))
      (node (ref "U11") (pin "6") (pinfunction "DIN1-_6") (pintype "passive"))
      (node (ref "U5") (pin "2") (pinfunction "D-_2") (pintype "passive"))
    )
    (net (code "22") (name "/TX5_P") (class "Default")
      (node (ref "CN2") (pin "9") (pinfunction "9_9") (pintype "passive"))
      (node (ref "R5") (pin "2") (pinfunction "2_2") (pintype "passive"))
      (node (ref "U11") (pin "5") (pinfunction "DIN1+_5") (pintype "passive"))
      (node (ref "U5") (pin "1") (pinfunction "D+_1") (pintype "passive"))
    )
    (net (code "23") (name "/TX6_ISO_N") (class "Default")
      (node (ref "CN4") (pin "6") (pinfunction "6_6") (pintype "passive"))
      (node (ref "R14") (pin "1") (pinfunction "1_1") (pintype "passive"))
      (node (ref "U11") (pin "13") (pinfunction "DOUT2-_13") (pintype "passive"))
      (node (ref "U18") (pin "1") (pinfunction "D+_1") (pintype "passive"))
    )
    (net (code "24") (name "/TX6_ISO_P") (class "Default")
      (node (ref "CN4") (pin "7") (pinfunction "7_7") (pintype "passive"))
      (node (ref "R14") (pin "2") (pinfunction "2_2") (pintype "passive"))
      (node (ref "U11") (pin "14") (pinfunction "DOUT2+_14") (pintype "passive"))
      (node (ref "U18") (pin "2") (pinfunction "D-_2") (pintype "passive"))
    )
    (net (code "25") (name "/TX6_N") (class "Default")
      (node (ref "CN2") (pin "6") (pinfunction "6_6") (pintype "passive"))
      (node (ref "R6") (pin "1") (pinfunction "1_1") (pintype "passive"))
      (node (ref "U11") (pin "8") (pinfunction "DIN2-_8") (pintype "passive"))
      (node (ref "U6") (pin "2") (pinfunction "D-_2") (pintype "passive"))
    )
    (net (code "26") (name "/TX6_P") (class "Default")
      (node (ref "CN2") (pin "7") (pinfunction "7_7") (pintype "passive"))
      (node (ref "R6") (pin "2") (pinfunction "2_2") (pintype "passive"))
      (node (ref "U11") (pin "7") (pinfunction "DIN2+_7") (pintype "passive"))
      (node (ref "U6") (pin "1") (pinfunction "D+_1") (pintype "passive"))
    )
    (net (code "27") (name "/TX7_ISO_N") (class "Default")
      (node (ref "CN4") (pin "3") (pinfunction "3_3") (pintype "passive"))
      (node (ref "R15") (pin "1") (pinfunction "1_1") (pintype "passive"))
      (node (ref "U12") (pin "15") (pinfunction "DOUT1-_15") (pintype "passive"))
      (node (ref "U19") (pin "1") (pinfunction "D+_1") (pintype "passive"))
    )
    (net (code "28") (name "/TX7_ISO_P") (class "Default")
      (node (ref "CN4") (pin "5") (pinfunction "5_5") (pintype "passive"))
      (node (ref "R15") (pin "2") (pinfunction "2_2") (pintype "passive"))
      (node (ref "U12") (pin "16") (pinfunction "DOUT1+_16") (pintype "passive"))
      (node (ref "U19") (pin "2") (pinfunction "D-_2") (pintype "passive"))
    )
    (net (code "29") (name "/TX7_N") (class "Default")
      (node (ref "CN2") (pin "3") (pinfunction "3_3") (pintype "passive"))
      (node (ref "R7") (pin "1") (pinfunction "1_1") (pintype "passive"))
      (node (ref "U12") (pin "6") (pinfunction "DIN1-_6") (pintype "passive"))
      (node (ref "U7") (pin "2") (pinfunction "D-_2") (pintype "passive"))
    )
    (net (code "30") (name "/TX7_P") (class "Default")
      (node (ref "CN2") (pin "5") (pinfunction "5_5") (pintype "passive"))
      (node (ref "R7") (pin "2") (pinfunction "2_2") (pintype "passive"))
      (node (ref "U12") (pin "5") (pinfunction "DIN1+_5") (pintype "passive"))
      (node (ref "U7") (pin "1") (pinfunction "D+_1") (pintype "passive"))
    )
    (net (code "31") (name "/TX8_ISO_N") (class "Default")
      (node (ref "CN4") (pin "1") (pinfunction "1_1") (pintype "passive"))
      (node (ref "R16") (pin "1") (pinfunction "1_1") (pintype "passive"))
      (node (ref "U12") (pin "13") (pinfunction "DOUT2-_13") (pintype "passive"))
      (node (ref "U20") (pin "1") (pinfunction "D+_1") (pintype "passive"))
    )
    (net (code "32") (name "/TX8_ISO_P") (class "Default")
      (node (ref "CN4") (pin "2") (pinfunction "2_2") (pintype "passive"))
      (node (ref "R16") (pin "2") (pinfunction "2_2") (pintype "passive"))
      (node (ref "U12") (pin "14") (pinfunction "DOUT2+_14") (pintype "passive"))
      (node (ref "U20") (pin "2") (pinfunction "D-_2") (pintype "passive"))
    )
    (net (code "33") (name "/TX8_N") (class "Default")
      (node (ref "CN2") (pin "1") (pinfunction "1_1") (pintype "passive"))
      (node (ref "R8") (pin "1") (pinfunction "1_1") (pintype "passive"))
      (node (ref "U12") (pin "8") (pinfunction "DIN2-_8") (pintype "passive"))
      (node (ref "U8") (pin "2") (pinfunction "D-_2") (pintype "passive"))
    )
    (net (code "34") (name "/TX8_P") (class "Default")
      (node (ref "CN2") (pin "2") (pinfunction "2_2") (pintype "passive"))
      (node (ref "R8") (pin "2") (pinfunction "2_2") (pintype "passive"))
      (node (ref "U12") (pin "7") (pinfunction "DIN2+_7") (pintype "passive"))
      (node (ref "U8") (pin "1") (pinfunction "D+_1") (pintype "passive"))
    )
    (net (code "35") (name "/TX9_ISO_N") (class "Default")
      (node (ref "CN7") (pin "8") (pinfunction "8_8") (pintype "passive"))
      (node (ref "R25") (pin "1") (pinfunction "1_1") (pintype "passive"))
      (node (ref "U29") (pin "15") (pinfunction "DOUT1-_15") (pintype "passive"))
      (node (ref "U33") (pin "1") (pinfunction "D+_1") (pintype "passive"))
    )
    (net (code "36") (name "/TX9_ISO_P") (class "Default")
      (node (ref "CN7") (pin "9") (pinfunction "9_9") (pintype "passive"))
      (node (ref "R25") (pin "2") (pinfunction "2_2") (pintype "passive"))
      (node (ref "U29") (pin "16") (pinfunction "DOUT1+_16") (pintype "passive"))
      (node (ref "U33") (pin "2") (pinfunction "D-_2") (pintype "passive"))
    )
    (net (code "37") (name "/TX9_N") (class "Default")
      (node (ref "CN5") (pin "8") (pinfunction "8_8") (pintype "passive"))
      (node (ref "R17") (pin "1") (pinfunction "1_1") (pintype "passive"))
      (node (ref "U21") (pin "2") (pinfunction "D-_2") (pintype "passive"))
      (node (ref "U29") (pin "6") (pinfunction "DIN1-_6") (pintype "passive"))
    )
    (net (code "38") (name "/TX9_P") (class "Default")
      (node (ref "CN5") (pin "9") (pinfunction "9_9") (pintype "passive"))
      (node (ref "R17") (pin "2") (pinfunction "2_2") (pintype "passive"))
      (node (ref "U21") (pin "1") (pinfunction "D+_1") (pintype "passive"))
      (node (ref "U29") (pin "5") (pinfunction "DIN1+_5") (pintype "passive"))
    )
    (net (code "39") (name "/TX10_ISO_N") (class "Default")
      (node (ref "CN7") (pin "6") (pinfunction "6_6") (pintype "passive"))
      (node (ref "R26") (pin "1") (pinfunction "1_1") (pintype "passive"))
      (node (ref "U29") (pin "13") (pinfunction "DOUT2-_13") (pintype "passive"))
      (node (ref "U34") (pin "1") (pinfunction "D+_1") (pintype "passive"))
    )
    (net (code "40") (name "/TX10_ISO_P") (class "Default")
      (node (ref "CN7") (pin "7") (pinfunction "7_7") (pintype "passive"))
      (node (ref "R26") (pin "2") (pinfunction "2_2") (pintype "passive"))
      (node (ref "U29") (pin "14") (pinfunction "DOUT2+_14") (pintype "passive"))
      (node (ref "U34") (pin "2") (pinfunction "D-_2") (pintype "passive"))
    )
    (net (code "41") (name "/TX10_N") (class "Default")
      (node (ref "CN5") (pin "6") (pinfunction "6_6") (pintype "passive"))
      (node (ref "R18") (pin "1") (pinfunction "1_1") (pintype "passive"))
      (node (ref "U22") (pin "2") (pinfunction "D-_2") (pintype "passive"))
      (node (ref "U29") (pin "8") (pinfunction "DIN2-_8") (pintype "passive"))
    )
    (net (code "42") (name "/TX10_P") (class "Default")
      (node (ref "CN5") (pin "7") (pinfunction "7_7") (pintype "passive"))
      (node (ref "R18") (pin "2") (pinfunction "2_2") (pintype "passive"))
      (node (ref "U22") (pin "1") (pinfunction "D+_1") (pintype "passive"))
      (node (ref "U29") (pin "7") (pinfunction "DIN2+_7") (pintype "passive"))
    )
    (net (code "43") (name "/TX11_ISO_N") (class "Default")
      (node (ref "CN7") (pin "3") (pinfunction "3_3") (pintype "passive"))
      (node (ref "R27") (pin "1") (pinfunction "1_1") (pintype "passive"))
      (node (ref "U30") (pin "15") (pinfunction "DOUT1-_15") (pintype "passive"))
      (node (ref "U35") (pin "1") (pinfunction "D+_1") (pintype "passive"))
    )
    (net (code "44") (name "/TX11_ISO_P") (class "Default")
      (node (ref "CN7") (pin "5") (pinfunction "5_5") (pintype "passive"))
      (node (ref "R27") (pin "2") (pinfunction "2_2") (pintype "passive"))
      (node (ref "U30") (pin "16") (pinfunction "DOUT1+_16") (pintype "passive"))
      (node (ref "U35") (pin "2") (pinfunction "D-_2") (pintype "passive"))
    )
    (net (code "45") (name "/TX11_N") (class "Default")
      (node (ref "CN5") (pin "3") (pinfunction "3_3") (pintype "passive"))
      (node (ref "R19") (pin "1") (pinfunction "1_1") (pintype "passive"))
      (node (ref "U23") (pin "2") (pinfunction "D-_2") (pintype "passive"))
      (node (ref "U30") (pin "6") (pinfunction "DIN1-_6") (pintype "passive"))
    )
    (net (code "46") (name "/TX11_P") (class "Default")
      (node (ref "CN5") (pin "5") (pinfunction "5_5") (pintype "passive"))
      (node (ref "R19") (pin "2") (pinfunction "2_2") (pintype "passive"))
      (node (ref "U23") (pin "1") (pinfunction "D+_1") (pintype "passive"))
      (node (ref "U30") (pin "5") (pinfunction "DIN1+_5") (pintype "passive"))
    )
    (net (code "47") (name "/TX12_ISO_N") (class "Default")
      (node (ref "CN7") (pin "1") (pinfunction "1_1") (pintype "passive"))
      (node (ref "R28") (pin "1") (pinfunction "1_1") (pintype "passive"))
      (node (ref "U30") (pin "13") (pinfunction "DOUT2-_13") (pintype "passive"))
      (node (ref "U36") (pin "1") (pinfunction "D+_1") (pintype "passive"))
    )
    (net (code "48") (name "/TX12_ISO_P") (class "Default")
      (node (ref "CN7") (pin "2") (pinfunction "2_2") (pintype "passive"))
      (node (ref "R28") (pin "2") (pinfunction "2_2") (pintype "passive"))
      (node (ref "U30") (pin "14") (pinfunction "DOUT2+_14") (pintype "passive"))
      (node (ref "U36") (pin "2") (pinfunction "D-_2") (pintype "passive"))
    )
    (net (code "49") (name "/TX12_N") (class "Default")
      (node (ref "CN5") (pin "1") (pinfunction "1_1") (pintype "passive"))
      (node (ref "R20") (pin "1") (pinfunction "1_1") (pintype "passive"))
      (node (ref "U24") (pin "2") (pinfunction "D-_2") (pintype "passive"))
      (node (ref "U30") (pin "8") (pinfunction "DIN2-_8") (pintype "passive"))
    )
    (net (code "50") (name "/TX12_P") (class "Default")
      (node (ref "CN5") (pin "2") (pinfunction "2_2") (pintype "passive"))
      (node (ref "R20") (pin "2") (pinfunction "2_2") (pintype "passive"))
      (node (ref "U24") (pin "1") (pinfunction "D+_1") (pintype "passive"))
      (node (ref "U30") (pin "7") (pinfunction "DIN2+_7") (pintype "passive"))
    )
    (net (code "51") (name "/TX13_ISO_N") (class "Default")
      (node (ref "CN8") (pin "8") (pinfunction "8_8") (pintype "passive"))
      (node (ref "R29") (pin "1") (pinfunction "1_1") (pintype "passive"))
      (node (ref "U31") (pin "15") (pinfunction "DOUT1-_15") (pintype "passive"))
      (node (ref "U37") (pin "1") (pinfunction "D+_1") (pintype "passive"))
    )
    (net (code "52") (name "/TX13_ISO_P") (class "Default")
      (node (ref "CN8") (pin "9") (pinfunction "9_9") (pintype "passive"))
      (node (ref "R29") (pin "2") (pinfunction "2_2") (pintype "passive"))
      (node (ref "U31") (pin "16") (pinfunction "DOUT1+_16") (pintype "passive"))
      (node (ref "U37") (pin "2") (pinfunction "D-_2") (pintype "passive"))
    )
    (net (code "53") (name "/TX13_N") (class "Default")
      (node (ref "CN6") (pin "8") (pinfunction "8_8") (pintype "passive"))
      (node (ref "R21") (pin "1") (pinfunction "1_1") (pintype "passive"))
      (node (ref "U25") (pin "2") (pinfunction "D-_2") (pintype "passive"))
      (node (ref "U31") (pin "6") (pinfunction "DIN1-_6") (pintype "passive"))
    )
    (net (code "54") (name "/TX13_P") (class "Default")
      (node (ref "CN6") (pin "9") (pinfunction "9_9") (pintype "passive"))
      (node (ref "R21") (pin "2") (pinfunction "2_2") (pintype "passive"))
      (node (ref "U25") (pin "1") (pinfunction "D+_1") (pintype "passive"))
      (node (ref "U31") (pin "5") (pinfunction "DIN1+_5") (pintype "passive"))
    )
    (net (code "55") (name "/TX14_ISO_N") (class "Default")
      (node (ref "CN8") (pin "6") (pinfunction "6_6") (pintype "passive"))
      (node (ref "R30") (pin "1") (pinfunction "1_1") (pintype "passive"))
      (node (ref "U31") (pin "13") (pinfunction "DOUT2-_13") (pintype "passive"))
      (node (ref "U38") (pin "1") (pinfunction "D+_1") (pintype "passive"))
    )
    (net (code "56") (name "/TX14_ISO_P") (class "Default")
      (node (ref "CN8") (pin "7") (pinfunction "7_7") (pintype "passive"))
      (node (ref "R30") (pin "2") (pinfunction "2_2") (pintype "passive"))
      (node (ref "U31") (pin "14") (pinfunction "DOUT2+_14") (pintype "passive"))
      (node (ref "U38") (pin "2") (pinfunction "D-_2") (pintype "passive"))
    )
    (net (code "57") (name "/TX14_N") (class "Default")
      (node (ref "CN6") (pin "6") (pinfunction "6_6") (pintype "passive"))
      (node (ref "R22") (pin "1") (pinfunction "1_1") (pintype "passive"))
      (node (ref "U26") (pin "2") (pinfunction "D-_2") (pintype "passive"))
      (node (ref "U31") (pin "8") (pinfunction "DIN2-_8") (pintype "passive"))
    )
    (net (code "58") (name "/TX14_P") (class "Default")
      (node (ref "CN6") (pin "7") (pinfunction "7_7") (pintype "passive"))
      (node (ref "R22") (pin "2") (pinfunction "2_2") (pintype "passive"))
      (node (ref "U26") (pin "1") (pinfunction "D+_1") (pintype "passive"))
      (node (ref "U31") (pin "7") (pinfunction "DIN2+_7") (pintype "passive"))
    )
    (net (code "59") (name "/TX15_ISO_N") (class "Default")
      (node (ref "CN8") (pin "3") (pinfunction "3_3") (pintype "passive"))
      (node (ref "R31") (pin "1") (pinfunction "1_1") (pintype "passive"))
      (node (ref "U32") (pin "15") (pinfunction "DOUT1-_15") (pintype "passive"))
      (node (ref "U39") (pin "1") (pinfunction "D+_1") (pintype "passive"))
    )
    (net (code "60") (name "/TX15_ISO_P") (class "Default")
      (node (ref "CN8") (pin "5") (pinfunction "5_5") (pintype "passive"))
      (node (ref "R31") (pin "2") (pinfunction "2_2") (pintype "passive"))
      (node (ref "U32") (pin "16") (pinfunction "DOUT1+_16") (pintype "passive"))
      (node (ref "U39") (pin "2") (pinfunction "D-_2") (pintype "passive"))
    )
    (net (code "61") (name "/TX15_N") (class "Default")
      (node (ref "CN6") (pin "3") (pinfunction "3_3") (pintype "passive"))
      (node (ref "R23") (pin "1") (pinfunction "1_1") (pintype "passive"))
      (node (ref "U27") (pin "2") (pinfunction "D-_2") (pintype "passive"))
      (node (ref "U32") (pin "6") (pinfunction "DIN1-_6") (pintype "passive"))
    )
    (net (code "62") (name "/TX15_P") (class "Default")
      (node (ref "CN6") (pin "5") (pinfunction "5_5") (pintype "passive"))
      (node (ref "R23") (pin "2") (pinfunction "2_2") (pintype "passive"))
      (node (ref "U27") (pin "1") (pinfunction "D+_1") (pintype "passive"))
      (node (ref "U32") (pin "5") (pinfunction "DIN1+_5") (pintype "passive"))
    )
    (net (code "63") (name "/TX16_ISO_N") (class "Default")
      (node (ref "CN8") (pin "1") (pinfunction "1_1") (pintype "passive"))
      (node (ref "R32") (pin "1") (pinfunction "1_1") (pintype "passive"))
      (node (ref "U32") (pin "13") (pinfunction "DOUT2-_13") (pintype "passive"))
      (node (ref "U40") (pin "1") (pinfunction "D+_1") (pintype "passive"))
    )
    (net (code "64") (name "/TX16_ISO_P") (class "Default")
      (node (ref "CN8") (pin "2") (pinfunction "2_2") (pintype "passive"))
      (node (ref "R32") (pin "2") (pinfunction "2_2") (pintype "passive"))
      (node (ref "U32") (pin "14") (pinfunction "DOUT2+_14") (pintype "passive"))
      (node (ref "U40") (pin "2") (pinfunction "D-_2") (pintype "passive"))
    )
    (net (code "65") (name "/TX16_N") (class "Default")
      (node (ref "CN6") (pin "1") (pinfunction "1_1") (pintype "passive"))
      (node (ref "R24") (pin "1") (pinfunction "1_1") (pintype "passive"))
      (node (ref "U28") (pin "2") (pinfunction "D-_2") (pintype "passive"))
      (node (ref "U32") (pin "8") (pinfunction "DIN2-_8") (pintype "passive"))
    )
    (net (code "66") (name "/TX16_P") (class "Default")
      (node (ref "CN6") (pin "2") (pinfunction "2_2") (pintype "passive"))
      (node (ref "R24") (pin "2") (pinfunction "2_2") (pintype "passive"))
      (node (ref "U28") (pin "1") (pinfunction "D+_1") (pintype "passive"))
      (node (ref "U32") (pin "7") (pinfunction "DIN2+_7") (pintype "passive"))
    )
    (net (code "67") (name "GND") (class "Default")
      (node (ref "C1") (pin "1") (pinfunction "1_1") (pintype "passive"))
      (node (ref "C10") (pin "2") (pinfunction "2_2") (pintype "passive"))
      (node (ref "C11") (pin "2") (pinfunction "2_2") (pintype "passive"))
      (node (ref "C12") (pin "2") (pinfunction "2_2") (pintype "passive"))
      (node (ref "C13") (pin "1") (pinfunction "1_1") (pintype "passive"))
      (node (ref "C14") (pin "1") (pinfunction "1_1") (pintype "passive"))
      (node (ref "C15") (pin "1") (pinfunction "1_1") (pintype "passive"))
      (node (ref "C16") (pin "1") (pinfunction "1_1") (pintype "passive"))
      (node (ref "C2") (pin "1") (pinfunction "1_1") (pintype "passive"))
      (node (ref "C3") (pin "1") (pinfunction "1_1") (pintype "passive"))
      (node (ref "C33") (pin "1") (pinfunction "1_1") (pintype "passive"))
      (node (ref "C34") (pin "1") (pinfunction "1_1") (pintype "passive"))
      (node (ref "C35") (pin "1") (pinfunction "1_1") (pintype "passive"))
      (node (ref "C36") (pin "1") (pinfunction "1_1") (pintype "passive"))
      (node (ref "C37") (pin "1") (pinfunction "1_1") (pintype "passive"))
      (node (ref "C38") (pin "1") (pinfunction "1_1") (pintype "passive"))
      (node (ref "C39") (pin "1") (pinfunction "1_1") (pintype "passive"))
      (node (ref "C4") (pin "1") (pinfunction "1_1") (pintype "passive"))
      (node (ref "C40") (pin "1") (pinfunction "1_1") (pintype "passive"))
      (node (ref "C41") (pin "2") (pinfunction "2_2") (pintype "passive"))
      (node (ref "C42") (pin "2") (pinfunction "2_2") (pintype "passive"))
      (node (ref "C43") (pin "2") (pinfunction "2_2") (pintype "passive"))
      (node (ref "C44") (pin "2") (pinfunction "2_2") (pintype "passive"))
      (node (ref "C45") (pin "1") (pinfunction "1_1") (pintype "passive"))
      (node (ref "C46") (pin "1") (pinfunction "1_1") (pintype "passive"))
      (node (ref "C47") (pin "1") (pinfunction "1_1") (pintype "passive"))
      (node (ref "C48") (pin "1") (pinfunction "1_1") (pintype "passive"))
      (node (ref "C5") (pin "1") (pinfunction "1_1") (pintype "passive"))
      (node (ref "C6") (pin "1") (pinfunction "1_1") (pintype "passive"))
      (node (ref "C7") (pin "1") (pinfunction "1_1") (pintype "passive"))
      (node (ref "C8") (pin "1") (pinfunction "1_1") (pintype "passive"))
      (node (ref "C9") (pin "2") (pinfunction "2_2") (pintype "passive"))
      (node (ref "U1") (pin "3") (pinfunction "GND_3") (pintype "power_in"))
      (node (ref "U10") (pin "10") (pinfunction "GND1_10") (pintype "passive"))
      (node (ref "U10") (pin "2") (pinfunction "GND1_2") (pintype "passive"))
      (node (ref "U10") (pin "4") (pinfunction "GND1_4") (pintype "passive"))
      (node (ref "U11") (pin "10") (pinfunction "GND1_10") (pintype "passive"))
      (node (ref "U11") (pin "2") (pinfunction "GND1_2") (pintype "passive"))
      (node (ref "U11") (pin "4") (pinfunction "GND1_4") (pintype "passive"))
      (node (ref "U12") (pin "10") (pinfunction "GND1_10") (pintype "passive"))
      (node (ref "U12") (pin "2") (pinfunction "GND1_2") (pintype "passive"))
      (node (ref "U12") (pin "4") (pinfunction "GND1_4") (pintype "passive"))
      (node (ref "U2") (pin "3") (pinfunction "GND_3") (pintype "power_in"))
      (node (ref "U21") (pin "3") (pinfunction "GND_3") (pintype "power_in"))
      (node (ref "U22") (pin "3") (pinfunction "GND_3") (pintype "power_in"))
      (node (ref "U23") (pin "3") (pinfunction "GND_3") (pintype "power_in"))
      (node (ref "U24") (pin "3") (pinfunction "GND_3") (pintype "power_in"))
      (node (ref "U25") (pin "3") (pinfunction "GND_3") (pintype "power_in"))
      (node (ref "U26") (pin "3") (pinfunction "GND_3") (pintype "power_in"))
      (node (ref "U27") (pin "3") (pinfunction "GND_3") (pintype "power_in"))
      (node (ref "U28") (pin "3") (pinfunction "GND_3") (pintype "power_in"))
      (node (ref "U29") (pin "10") (pinfunction "GND1_10") (pintype "passive"))
      (node (ref "U29") (pin "2") (pinfunction "GND1_2") (pintype "passive"))
      (node (ref "U29") (pin "4") (pinfunction "GND1_4") (pintype "passive"))
      (node (ref "U3") (pin "3") (pinfunction "GND_3") (pintype "power_in"))
      (node (ref "U30") (pin "10") (pinfunction "GND1_10") (pintype "passive"))
      (node (ref "U30") (pin "2") (pinfunction "GND1_2") (pintype "passive"))
      (node (ref "U30") (pin "4") (pinfunction "GND1_4") (pintype "passive"))
      (node (ref "U31") (pin "10") (pinfunction "GND1_10") (pintype "passive"))
      (node (ref "U31") (pin "2") (pinfunction "GND1_2") (pintype "passive"))
      (node (ref "U31") (pin "4") (pinfunction "GND1_4") (pintype "passive"))
      (node (ref "U32") (pin "10") (pinfunction "GND1_10") (pintype "passive"))
      (node (ref "U32") (pin "2") (pinfunction "GND1_2") (pintype "passive"))
      (node (ref "U32") (pin "4") (pinfunction "GND1_4") (pintype "passive"))
      (node (ref "U4") (pin "3") (pinfunction "GND_3") (pintype "power_in"))
      (node (ref "U5") (pin "3") (pinfunction "GND_3") (pintype "power_in"))
      (node (ref "U6") (pin "3") (pinfunction "GND_3") (pintype "power_in"))
      (node (ref "U7") (pin "3") (pinfunction "GND_3") (pintype "power_in"))
      (node (ref "U8") (pin "3") (pinfunction "GND_3") (pintype "power_in"))
      (node (ref "U9") (pin "10") (pinfunction "GND1_10") (pintype "passive"))
      (node (ref "U9") (pin "2") (pinfunction "GND1_2") (pintype "passive"))
      (node (ref "U9") (pin "4") (pinfunction "GND1_4") (pintype "passive"))
    )
    (net (code "68") (name "GND_ISO") (class "Default")
      (node (ref "C17") (pin "1") (pinfunction "1_1") (pintype "passive"))
      (node (ref "C18") (pin "1") (pinfunction "1_1") (pintype "passive"))
      (node (ref "C19") (pin "1") (pinfunction "1_1") (pintype "passive"))
      (node (ref "C20") (pin "1") (pinfunction "1_1") (pintype "passive"))
      (node (ref "C21") (pin "1") (pinfunction "1_1") (pintype "passive"))
      (node (ref "C22") (pin "1") (pinfunction "1_1") (pintype "passive"))
      (node (ref "C23") (pin "1") (pinfunction "1_1") (pintype "passive"))
      (node (ref "C24") (pin "1") (pinfunction "1_1") (pintype "passive"))
      (node (ref "C25") (pin "1") (pinfunction "1_1") (pintype "passive"))
      (node (ref "C26") (pin "1") (pinfunction "1_1") (pintype "passive"))
      (node (ref "C27") (pin "1") (pinfunction "1_1") (pintype "passive"))
      (node (ref "C28") (pin "1") (pinfunction "1_1") (pintype "passive"))
      (node (ref "C29") (pin "1") (pinfunction "1_1") (pintype "passive"))
      (node (ref "C30") (pin "1") (pinfunction "1_1") (pintype "passive"))
      (node (ref "C31") (pin "1") (pinfunction "1_1") (pintype "passive"))
      (node (ref "C32") (pin "1") (pinfunction "1_1") (pintype "passive"))
      (node (ref "C49") (pin "1") (pinfunction "1_1") (pintype "passive"))
      (node (ref "C50") (pin "1") (pinfunction "1_1") (pintype "passive"))
      (node (ref "C51") (pin "1") (pinfunction "1_1") (pintype "passive"))
      (node (ref "C52") (pin "1") (pinfunction "1_1") (pintype "passive"))
      (node (ref "C53") (pin "1") (pinfunction "1_1") (pintype "passive"))
      (node (ref "C54") (pin "1") (pinfunction "1_1") (pintype "passive"))
      (node (ref "C55") (pin "1") (pinfunction "1_1") (pintype "passive"))
      (node (ref "C56") (pin "1") (pinfunction "1_1") (pintype "passive"))
      (node (ref "C57") (pin "1") (pinfunction "1_1") (pintype "passive"))
      (node (ref "C58") (pin "1") (pinfunction "1_1") (pintype "passive"))
      (node (ref "C59") (pin "1") (pinfunction "1_1") (pintype "passive"))
      (node (ref "C60") (pin "1") (pinfunction "1_1") (pintype "passive"))
      (node (ref "C61") (pin "1") (pinfunction "1_1") (pintype "passive"))
      (node (ref "C62") (pin "1") (pinfunction "1_1") (pintype "passive"))
      (node (ref "C63") (pin "1") (pinfunction "1_1") (pintype "passive"))
      (node (ref "C64") (pin "1") (pinfunction "1_1") (pintype "passive"))
      (node (ref "U10") (pin "11") (pinfunction "GND2_11") (pintype "passive"))
      (node (ref "U10") (pin "17") (pinfunction "GND2_17") (pintype "passive"))
      (node (ref "U10") (pin "19") (pinfunction "GND2_19") (pintype "passive"))
      (node (ref "U11") (pin "11") (pinfunction "GND2_11") (pintype "passive"))
      (node (ref "U11") (pin "17") (pinfunction "GND2_17") (pintype "passive"))
      (node (ref "U11") (pin "19") (pinfunction "GND2_19") (pintype "passive"))
      (node (ref "U12") (pin "11") (pinfunction "GND2_11") (pintype "passive"))
      (node (ref "U12") (pin "17") (pinfunction "GND2_17") (pintype "passive"))
      (node (ref "U12") (pin "19") (pinfunction "GND2_19") (pintype "passive"))
      (node (ref "U13") (pin "3") (pinfunction "GND_3") (pintype "power_in"))
      (node (ref "U14") (pin "3") (pinfunction "GND_3") (pintype "power_in"))
      (node (ref "U15") (pin "3") (pinfunction "GND_3") (pintype "power_in"))
      (node (ref "U16") (pin "3") (pinfunction "GND_3") (pintype "power_in"))
      (node (ref "U17") (pin "3") (pinfunction "GND_3") (pintype "power_in"))
      (node (ref "U18") (pin "3") (pinfunction "GND_3") (pintype "power_in"))
      (node (ref "U19") (pin "3") (pinfunction "GND_3") (pintype "power_in"))
      (node (ref "U20") (pin "3") (pinfunction "GND_3") (pintype "power_in"))
      (node (ref "U29") (pin "11") (pinfunction "GND2_11") (pintype "passive"))
      (node (ref "U29") (pin "17") (pinfunction "GND2_17") (pintype "passive"))
      (node (ref "U29") (pin "19") (pinfunction "GND2_19") (pintype "passive"))
      (node (ref "U30") (pin "11") (pinfunction "GND2_11") (pintype "passive"))
      (node (ref "U30") (pin "17") (pinfunction "GND2_17") (pintype "passive"))
      (node (ref "U30") (pin "19") (pinfunction "GND2_19") (pintype "passive"))
      (node (ref "U31") (pin "11") (pinfunction "GND2_11") (pintype "passive"))
      (node (ref "U31") (pin "17") (pinfunction "GND2_17") (pintype "passive"))
      (node (ref "U31") (pin "19") (pinfunction "GND2_19") (pintype "passive"))
      (node (ref "U32") (pin "11") (pinfunction "GND2_11") (pintype "passive"))
      (node (ref "U32") (pin "17") (pinfunction "GND2_17") (pintype "passive"))
      (node (ref "U32") (pin "19") (pinfunction "GND2_19") (pintype "passive"))
      (node (ref "U33") (pin "3") (pinfunction "GND_3") (pintype "power_in"))
      (node (ref "U34") (pin "3") (pinfunction "GND_3") (pintype "power_in"))
      (node (ref "U35") (pin "3") (pinfunction "GND_3") (pintype "power_in"))
      (node (ref "U36") (pin "3") (pinfunction "GND_3") (pintype "power_in"))
      (node (ref "U37") (pin "3") (pinfunction "GND_3") (pintype "power_in"))
      (node (ref "U38") (pin "3") (pinfunction "GND_3") (pintype "power_in"))
      (node (ref "U39") (pin "3") (pinfunction "GND_3") (pintype "power_in"))
      (node (ref "U40") (pin "3") (pinfunction "GND_3") (pintype "power_in"))
      (node (ref "U9") (pin "11") (pinfunction "GND2_11") (pintype "passive"))
      (node (ref "U9") (pin "17") (pinfunction "GND2_17") (pintype "passive"))
      (node (ref "U9") (pin "19") (pinfunction "GND2_19") (pintype "passive"))
    )
    (net (code "69") (name "Net-(C1-Pad2)") (class "Default")
      (node (ref "C1") (pin "2") (pinfunction "2_2") (pintype "passive"))
      (node (ref "C13") (pin "2") (pinfunction "2_2") (pintype "passive"))
      (node (ref "C5") (pin "2") (pinfunction "2_2") (pintype "passive"))
      (node (ref "U9") (pin "3") (pinfunction "VDD1_3") (pintype "passive"))
      (node (ref "U9") (pin "9") (pinfunction "VDD1_9") (pintype "passive"))
    )
    (net (code "70") (name "Net-(C14-Pad2)") (class "Default")
      (node (ref "C14") (pin "2") (pinfunction "2_2") (pintype "passive"))
      (node (ref "C2") (pin "2") (pinfunction "2_2") (pintype "passive"))
      (node (ref "C6") (pin "2") (pinfunction "2_2") (pintype "passive"))
      (node (ref "U10") (pin "3") (pinfunction "VDD1_3") (pintype "passive"))
      (node (ref "U10") (pin "9") (pinfunction "VDD1_9") (pintype "passive"))
    )
    (net (code "71") (name "Net-(C15-Pad2)") (class "Default")
      (node (ref "C15") (pin "2") (pinfunction "2_2") (pintype "passive"))
      (node (ref "C3") (pin "2") (pinfunction "2_2") (pintype "passive"))
      (node (ref "C7") (pin "2") (pinfunction "2_2") (pintype "passive"))
      (node (ref "U11") (pin "3") (pinfunction "VDD1_3") (pintype "passive"))
      (node (ref "U11") (pin "9") (pinfunction "VDD1_9") (pintype "passive"))
    )
    (net (code "72") (name "Net-(C16-Pad2)") (class "Default")
      (node (ref "C16") (pin "2") (pinfunction "2_2") (pintype "passive"))
      (node (ref "C4") (pin "2") (pinfunction "2_2") (pintype "passive"))
      (node (ref "C8") (pin "2") (pinfunction "2_2") (pintype "passive"))
      (node (ref "U12") (pin "3") (pinfunction "VDD1_3") (pintype "passive"))
      (node (ref "U12") (pin "9") (pinfunction "VDD1_9") (pintype "passive"))
    )
    (net (code "73") (name "Net-(C21-Pad2)") (class "Default")
      (node (ref "C21") (pin "2") (pinfunction "2_2") (pintype "passive"))
      (node (ref "C25") (pin "2") (pinfunction "2_2") (pintype "passive"))
      (node (ref "C29") (pin "2") (pinfunction "2_2") (pintype "passive"))
      (node (ref "U9") (pin "12") (pinfunction "VDD2_12") (pintype "passive"))
      (node (ref "U9") (pin "18") (pinfunction "VDD2_18") (pintype "passive"))
    )
    (net (code "74") (name "Net-(C22-Pad2)") (class "Default")
      (node (ref "C22") (pin "2") (pinfunction "2_2") (pintype "passive"))
      (node (ref "C26") (pin "2") (pinfunction "2_2") (pintype "passive"))
      (node (ref "C30") (pin "2") (pinfunction "2_2") (pintype "passive"))
      (node (ref "U10") (pin "12") (pinfunction "VDD2_12") (pintype "passive"))
      (node (ref "U10") (pin "18") (pinfunction "VDD2_18") (pintype "passive"))
    )
    (net (code "75") (name "Net-(C23-Pad2)") (class "Default")
      (node (ref "C23") (pin "2") (pinfunction "2_2") (pintype "passive"))
      (node (ref "C27") (pin "2") (pinfunction "2_2") (pintype "passive"))
      (node (ref "C31") (pin "2") (pinfunction "2_2") (pintype "passive"))
      (node (ref "U11") (pin "12") (pinfunction "VDD2_12") (pintype "passive"))
      (node (ref "U11") (pin "18") (pinfunction "VDD2_18") (pintype "passive"))
    )
    (net (code "76") (name "Net-(C24-Pad2)") (class "Default")
      (node (ref "C24") (pin "2") (pinfunction "2_2") (pintype "passive"))
      (node (ref "C28") (pin "2") (pinfunction "2_2") (pintype "passive"))
      (node (ref "C32") (pin "2") (pinfunction "2_2") (pintype "passive"))
      (node (ref "U12") (pin "12") (pinfunction "VDD2_12") (pintype "passive"))
      (node (ref "U12") (pin "18") (pinfunction "VDD2_18") (pintype "passive"))
    )
    (net (code "77") (name "Net-(C33-Pad2)") (class "Default")
      (node (ref "C33") (pin "2") (pinfunction "2_2") (pintype "passive"))
      (node (ref "C37") (pin "2") (pinfunction "2_2") (pintype "passive"))
      (node (ref "C45") (pin "2") (pinfunction "2_2") (pintype "passive"))
      (node (ref "U29") (pin "3") (pinfunction "VDD1_3") (pintype "passive"))
      (node (ref "U29") (pin "9") (pinfunction "VDD1_9") (pintype "passive"))
    )
    (net (code "78") (name "Net-(C34-Pad2)") (class "Default")
      (node (ref "C34") (pin "2") (pinfunction "2_2") (pintype "passive"))
      (node (ref "C38") (pin "2") (pinfunction "2_2") (pintype "passive"))
      (node (ref "C46") (pin "2") (pinfunction "2_2") (pintype "passive"))
      (node (ref "U30") (pin "3") (pinfunction "VDD1_3") (pintype "passive"))
      (node (ref "U30") (pin "9") (pinfunction "VDD1_9") (pintype "passive"))
    )
    (net (code "79") (name "Net-(C35-Pad2)") (class "Default")
      (node (ref "C35") (pin "2") (pinfunction "2_2") (pintype "passive"))
      (node (ref "C39") (pin "2") (pinfunction "2_2") (pintype "passive"))
      (node (ref "C47") (pin "2") (pinfunction "2_2") (pintype "passive"))
      (node (ref "U31") (pin "3") (pinfunction "VDD1_3") (pintype "passive"))
      (node (ref "U31") (pin "9") (pinfunction "VDD1_9") (pintype "passive"))
    )
    (net (code "80") (name "Net-(C36-Pad2)") (class "Default")
      (node (ref "C36") (pin "2") (pinfunction "2_2") (pintype "passive"))
      (node (ref "C40") (pin "2") (pinfunction "2_2") (pintype "passive"))
      (node (ref "C48") (pin "2") (pinfunction "2_2") (pintype "passive"))
      (node (ref "U32") (pin "3") (pinfunction "VDD1_3") (pintype "passive"))
      (node (ref "U32") (pin "9") (pinfunction "VDD1_9") (pintype "passive"))
    )
    (net (code "81") (name "Net-(C53-Pad2)") (class "Default")
      (node (ref "C53") (pin "2") (pinfunction "2_2") (pintype "passive"))
      (node (ref "C57") (pin "2") (pinfunction "2_2") (pintype "passive"))
      (node (ref "C61") (pin "2") (pinfunction "2_2") (pintype "passive"))
      (node (ref "U29") (pin "12") (pinfunction "VDD2_12") (pintype "passive"))
      (node (ref "U29") (pin "18") (pinfunction "VDD2_18") (pintype "passive"))
    )
    (net (code "82") (name "Net-(C54-Pad2)") (class "Default")
      (node (ref "C54") (pin "2") (pinfunction "2_2") (pintype "passive"))
      (node (ref "C58") (pin "2") (pinfunction "2_2") (pintype "passive"))
      (node (ref "C62") (pin "2") (pinfunction "2_2") (pintype "passive"))
      (node (ref "U30") (pin "12") (pinfunction "VDD2_12") (pintype "passive"))
      (node (ref "U30") (pin "18") (pinfunction "VDD2_18") (pintype "passive"))
    )
    (net (code "83") (name "Net-(C55-Pad2)") (class "Default")
      (node (ref "C55") (pin "2") (pinfunction "2_2") (pintype "passive"))
      (node (ref "C59") (pin "2") (pinfunction "2_2") (pintype "passive"))
      (node (ref "C63") (pin "2") (pinfunction "2_2") (pintype "passive"))
      (node (ref "U31") (pin "12") (pinfunction "VDD2_12") (pintype "passive"))
      (node (ref "U31") (pin "18") (pinfunction "VDD2_18") (pintype "passive"))
    )
    (net (code "84") (name "Net-(C56-Pad2)") (class "Default")
      (node (ref "C56") (pin "2") (pinfunction "2_2") (pintype "passive"))
      (node (ref "C60") (pin "2") (pinfunction "2_2") (pintype "passive"))
      (node (ref "C64") (pin "2") (pinfunction "2_2") (pintype "passive"))
      (node (ref "U32") (pin "12") (pinfunction "VDD2_12") (pintype "passive"))
      (node (ref "U32") (pin "18") (pinfunction "VDD2_18") (pintype "passive"))
    )
    (net (code "85") (name "unconnected-(CN1-Pad4)") (class "Default")
      (node (ref "CN1") (pin "4") (pinfunction "4_4") (pintype "passive"))
    )
    (net (code "86") (name "unconnected-(CN2-Pad4)") (class "Default")
      (node (ref "CN2") (pin "4") (pinfunction "4_4") (pintype "passive"))
    )
    (net (code "87") (name "unconnected-(CN3-Pad4)") (class "Default")
      (node (ref "CN3") (pin "4") (pinfunction "4_4") (pintype "passive"))
    )
    (net (code "88") (name "unconnected-(CN4-Pad4)") (class "Default")
      (node (ref "CN4") (pin "4") (pinfunction "4_4") (pintype "passive"))
    )
    (net (code "89") (name "unconnected-(CN5-Pad4)") (class "Default")
      (node (ref "CN5") (pin "4") (pinfunction "4_4") (pintype "passive"))
    )
    (net (code "90") (name "unconnected-(CN6-Pad4)") (class "Default")
      (node (ref "CN6") (pin "4") (pinfunction "4_4") (pintype "passive"))
    )
    (net (code "91") (name "unconnected-(CN7-Pad4)") (class "Default")
      (node (ref "CN7") (pin "4") (pinfunction "4_4") (pintype "passive"))
    )
    (net (code "92") (name "unconnected-(CN8-Pad4)") (class "Default")
      (node (ref "CN8") (pin "4") (pinfunction "4_4") (pintype "passive"))
    )
  )
)
